# mcat-4cu-b-v2e.net
KiCad netlist of a schematic drawn in EAGLE
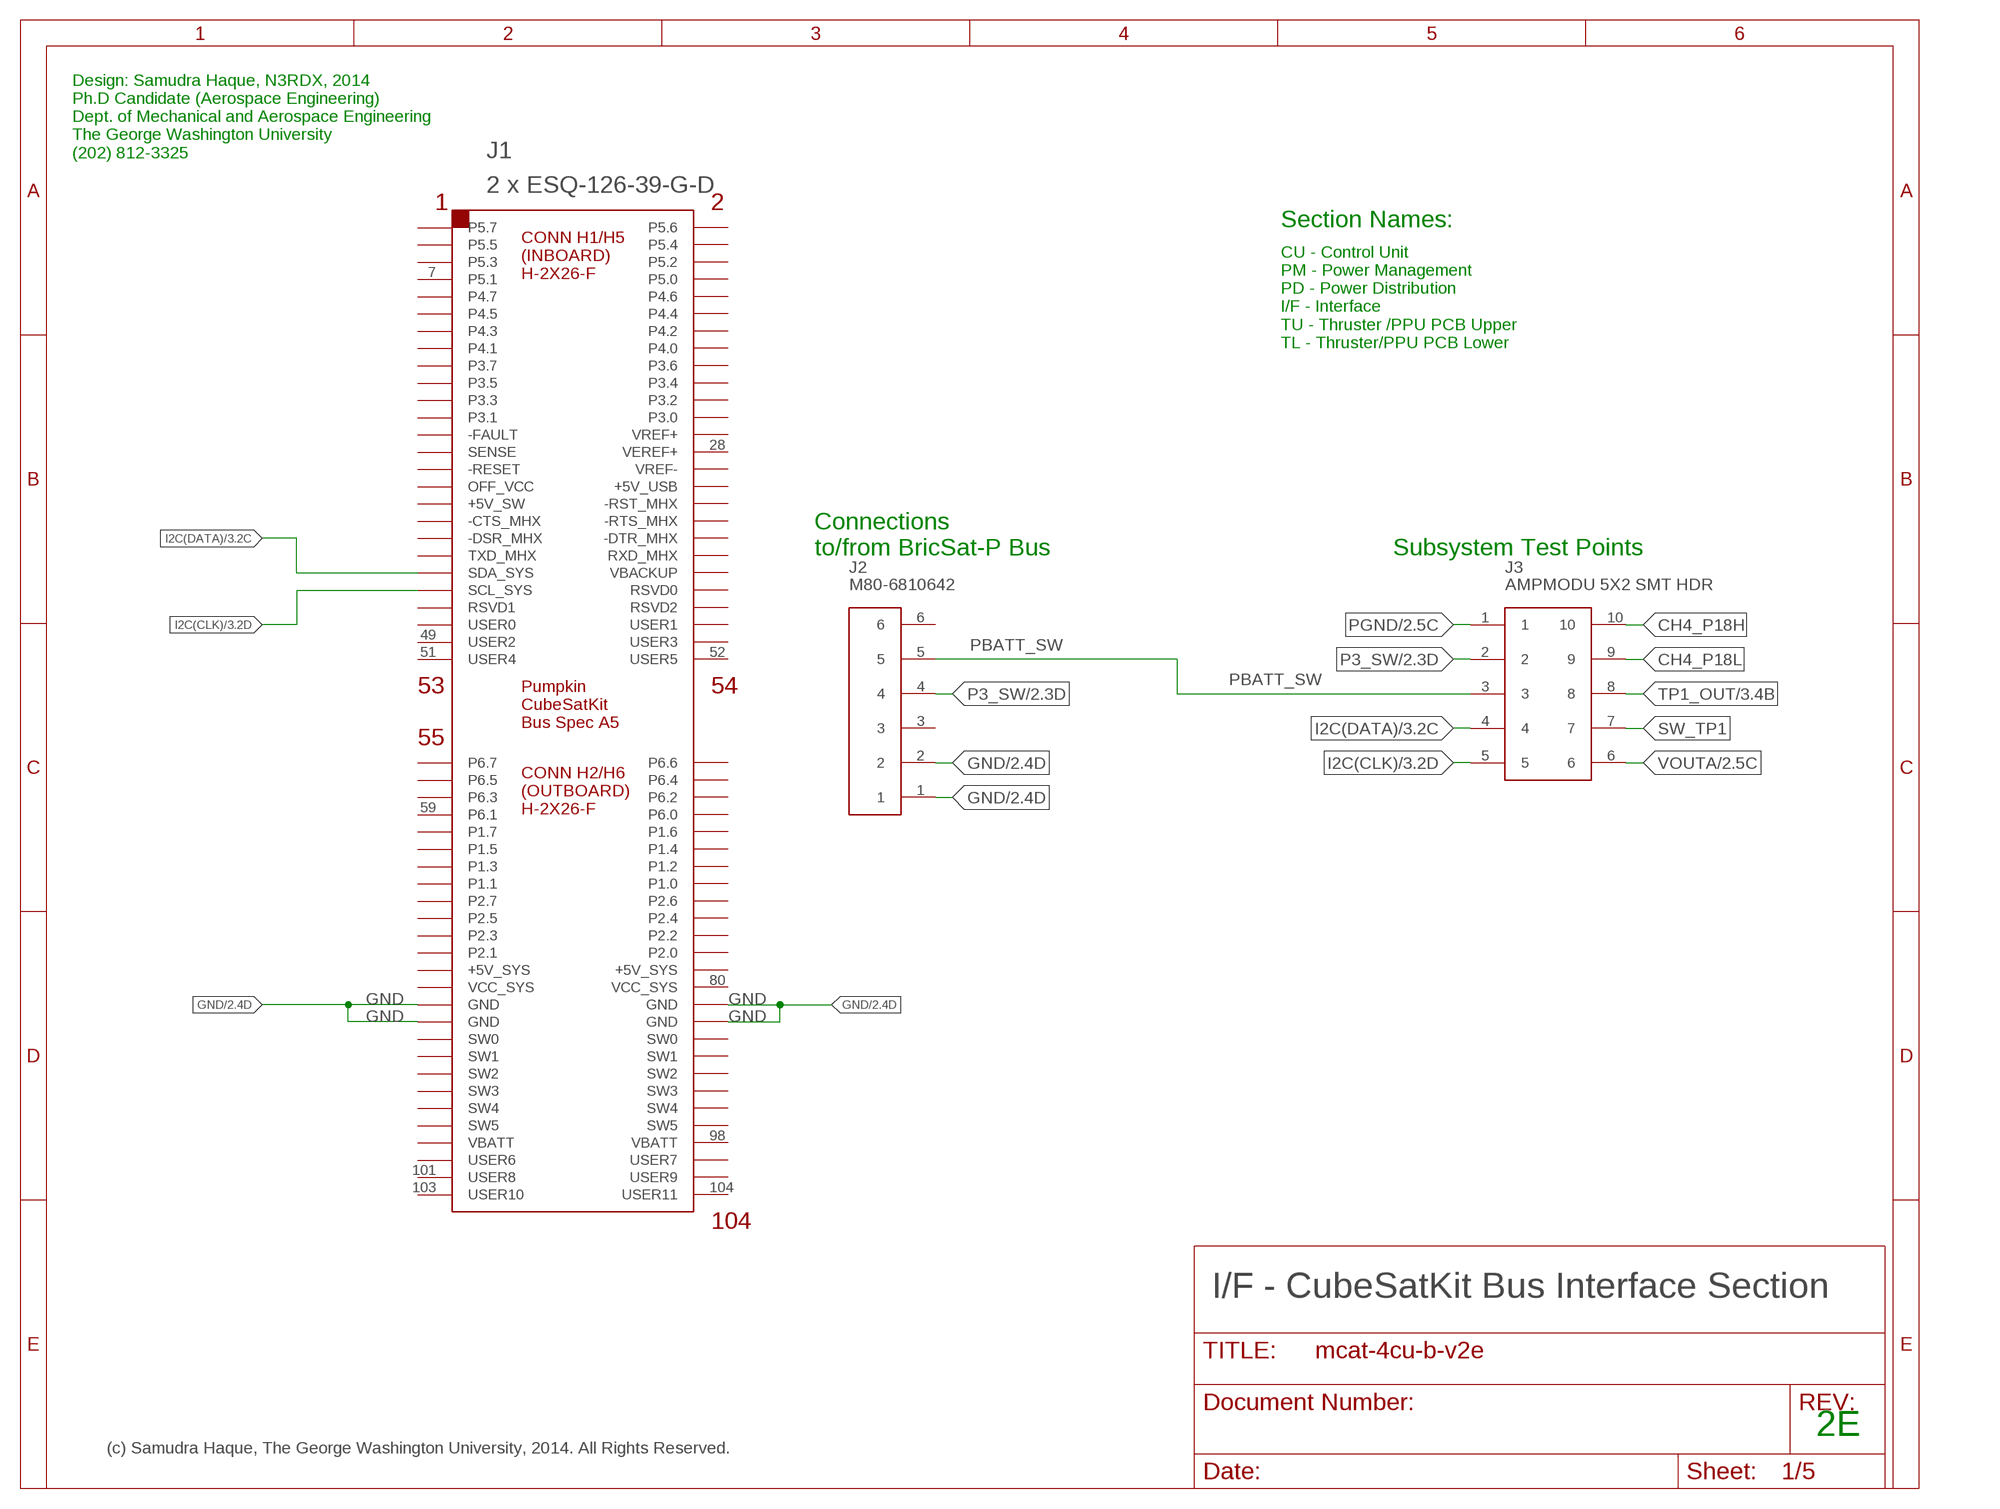
[diagram p0: schematic, sheet 1]
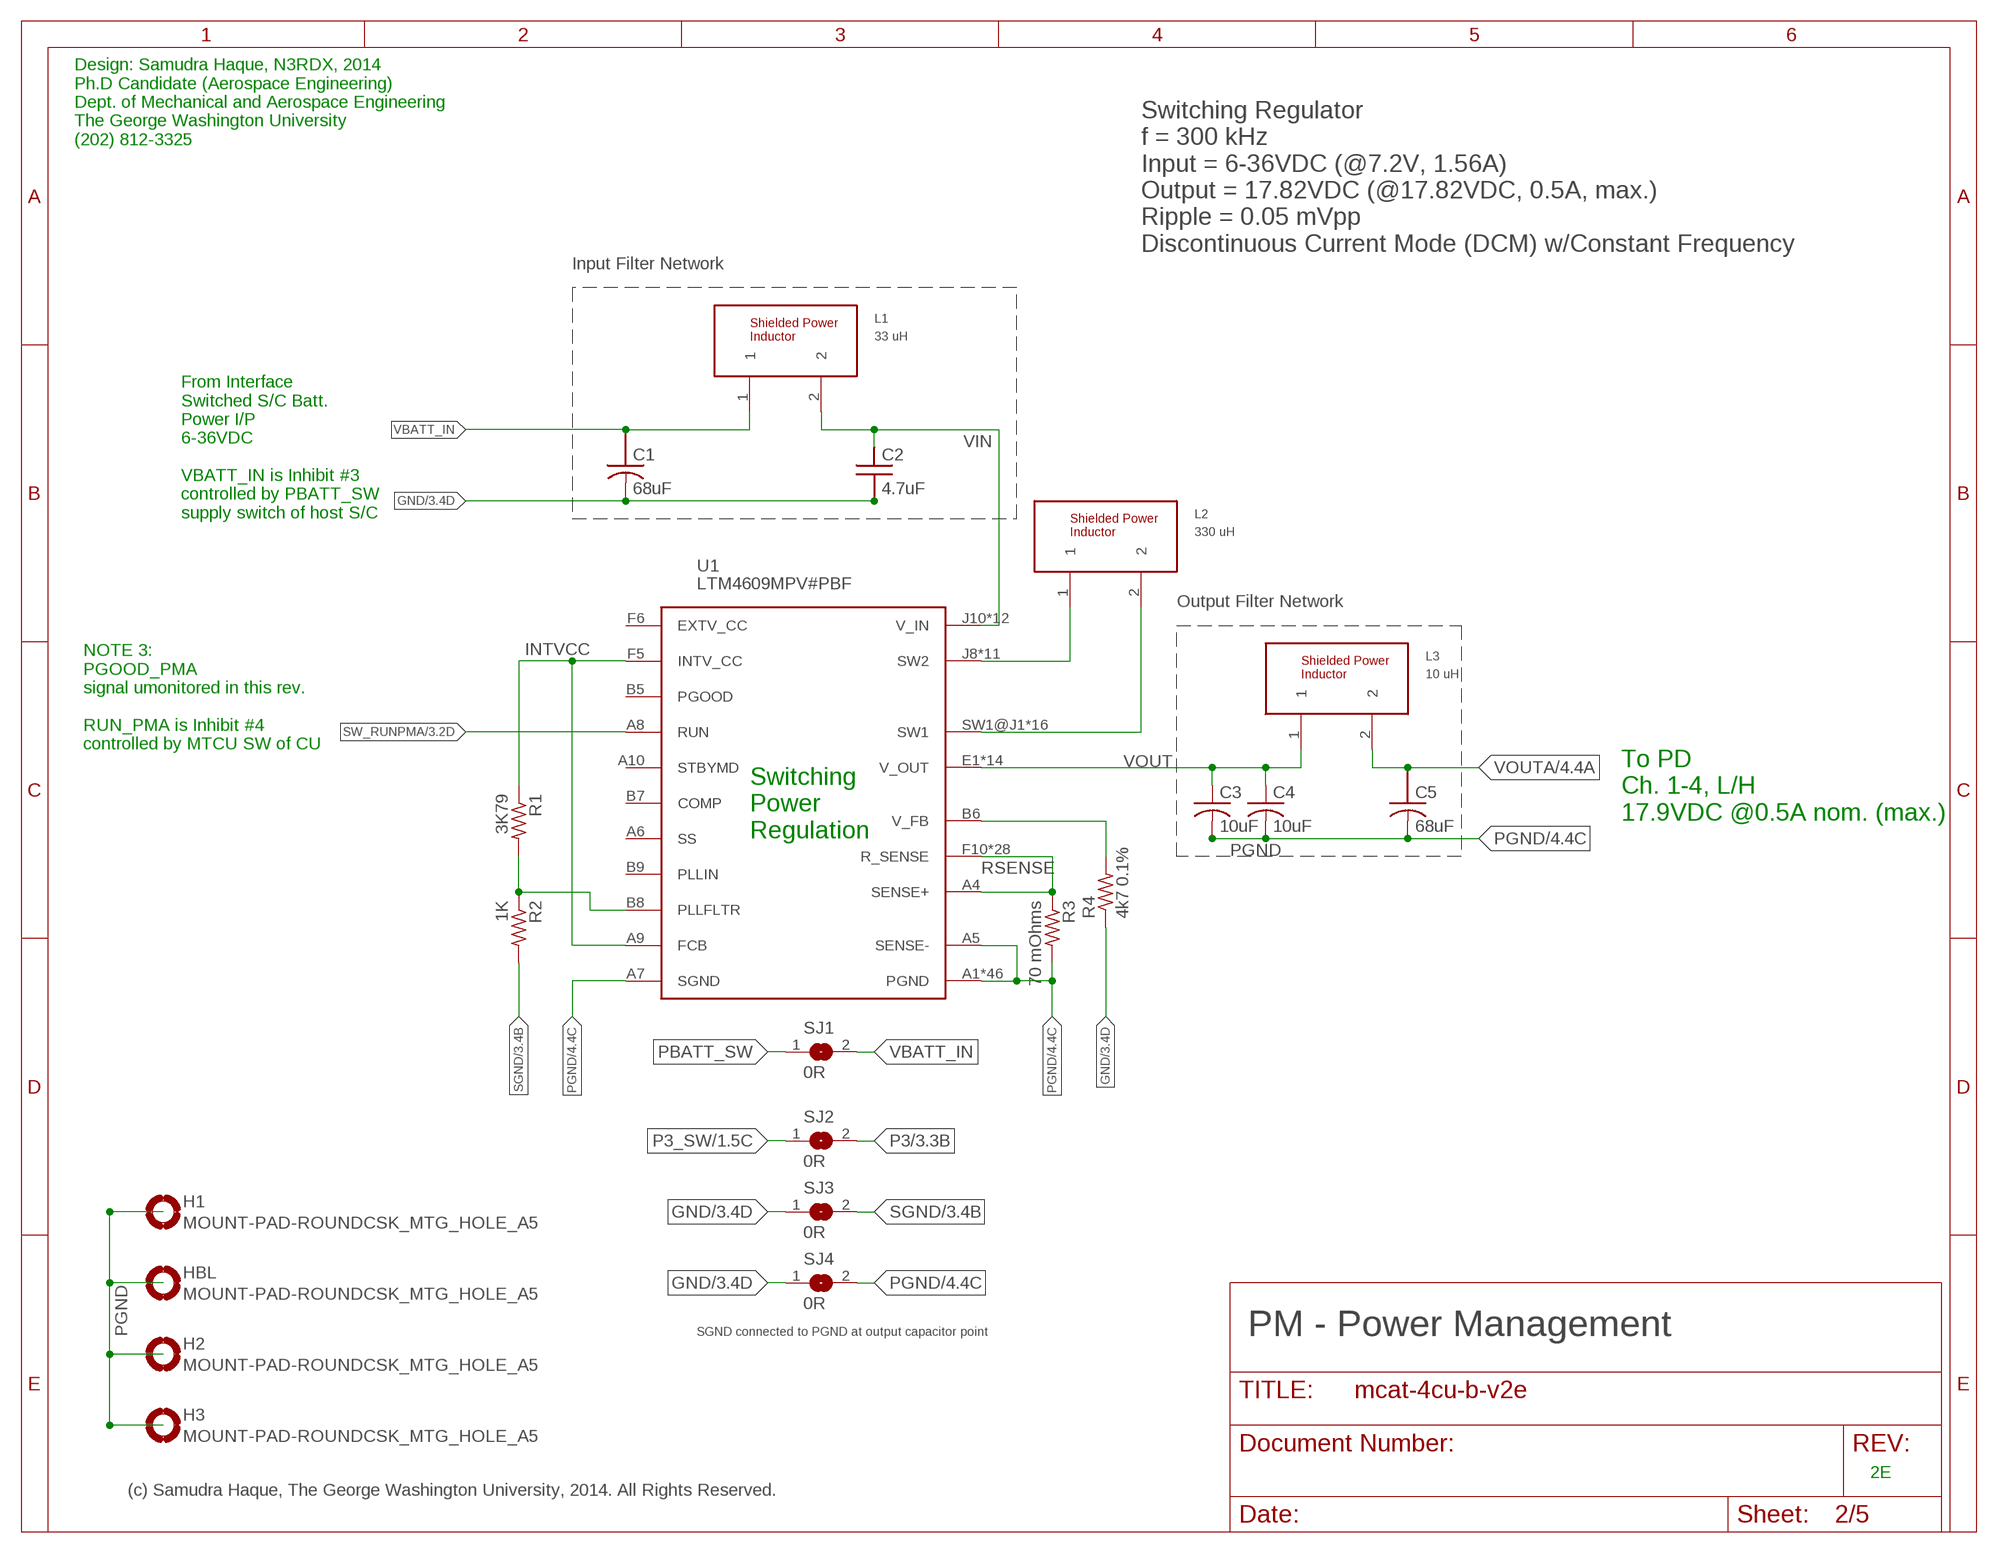
[diagram p1: schematic, sheet 2]
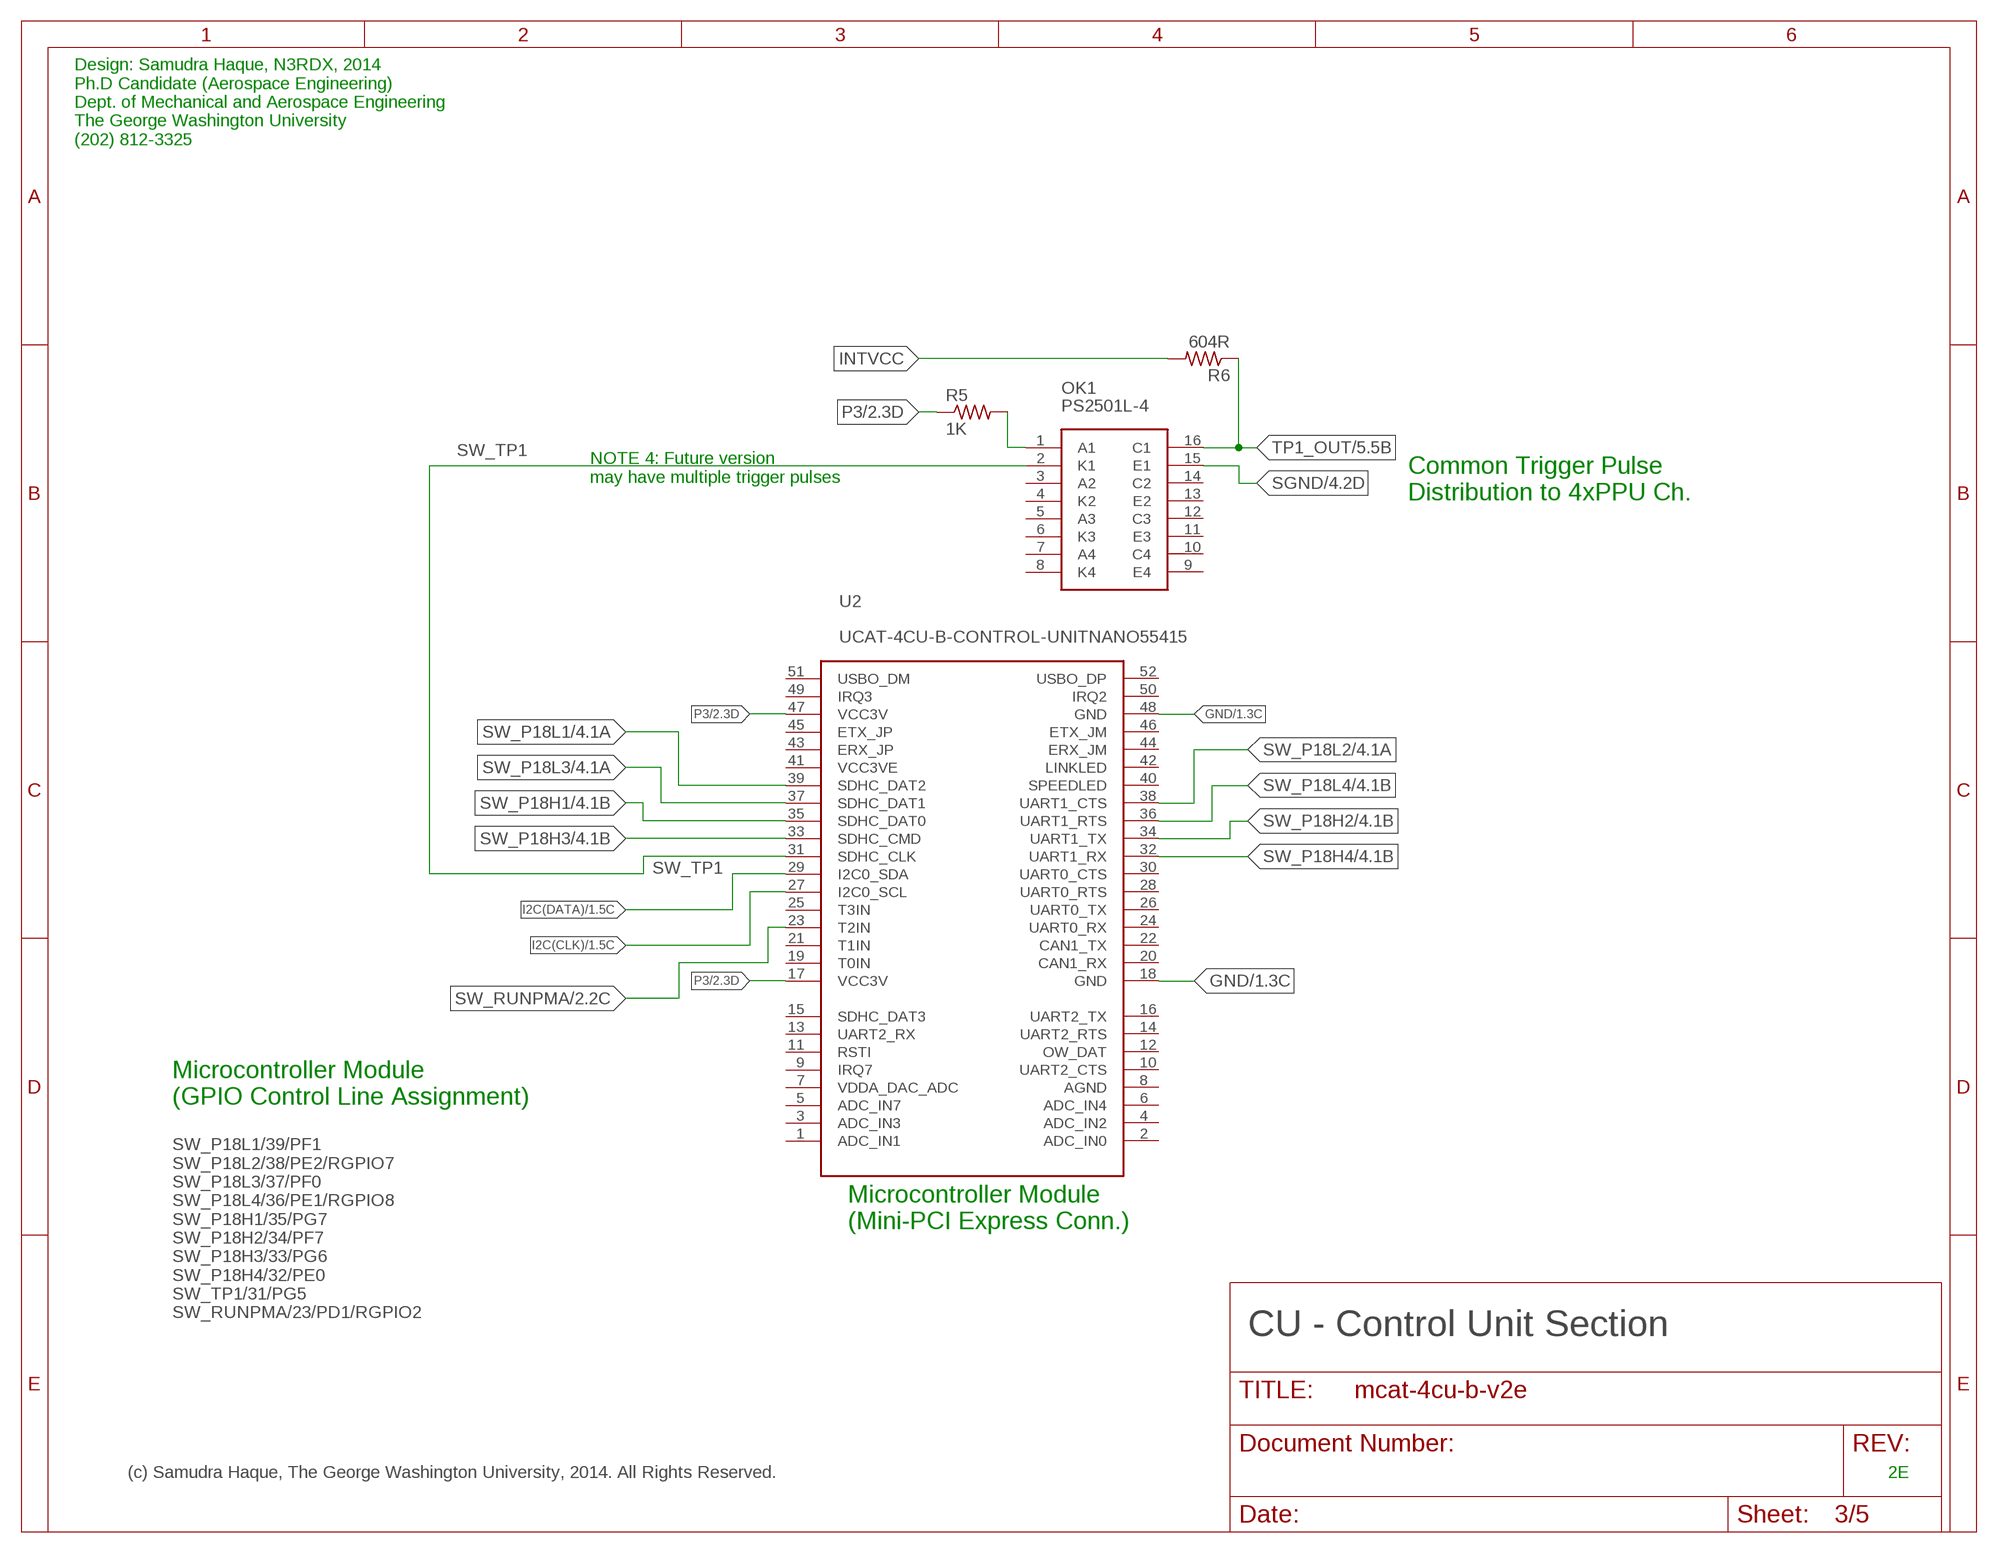
[diagram p2: schematic, sheet 3]
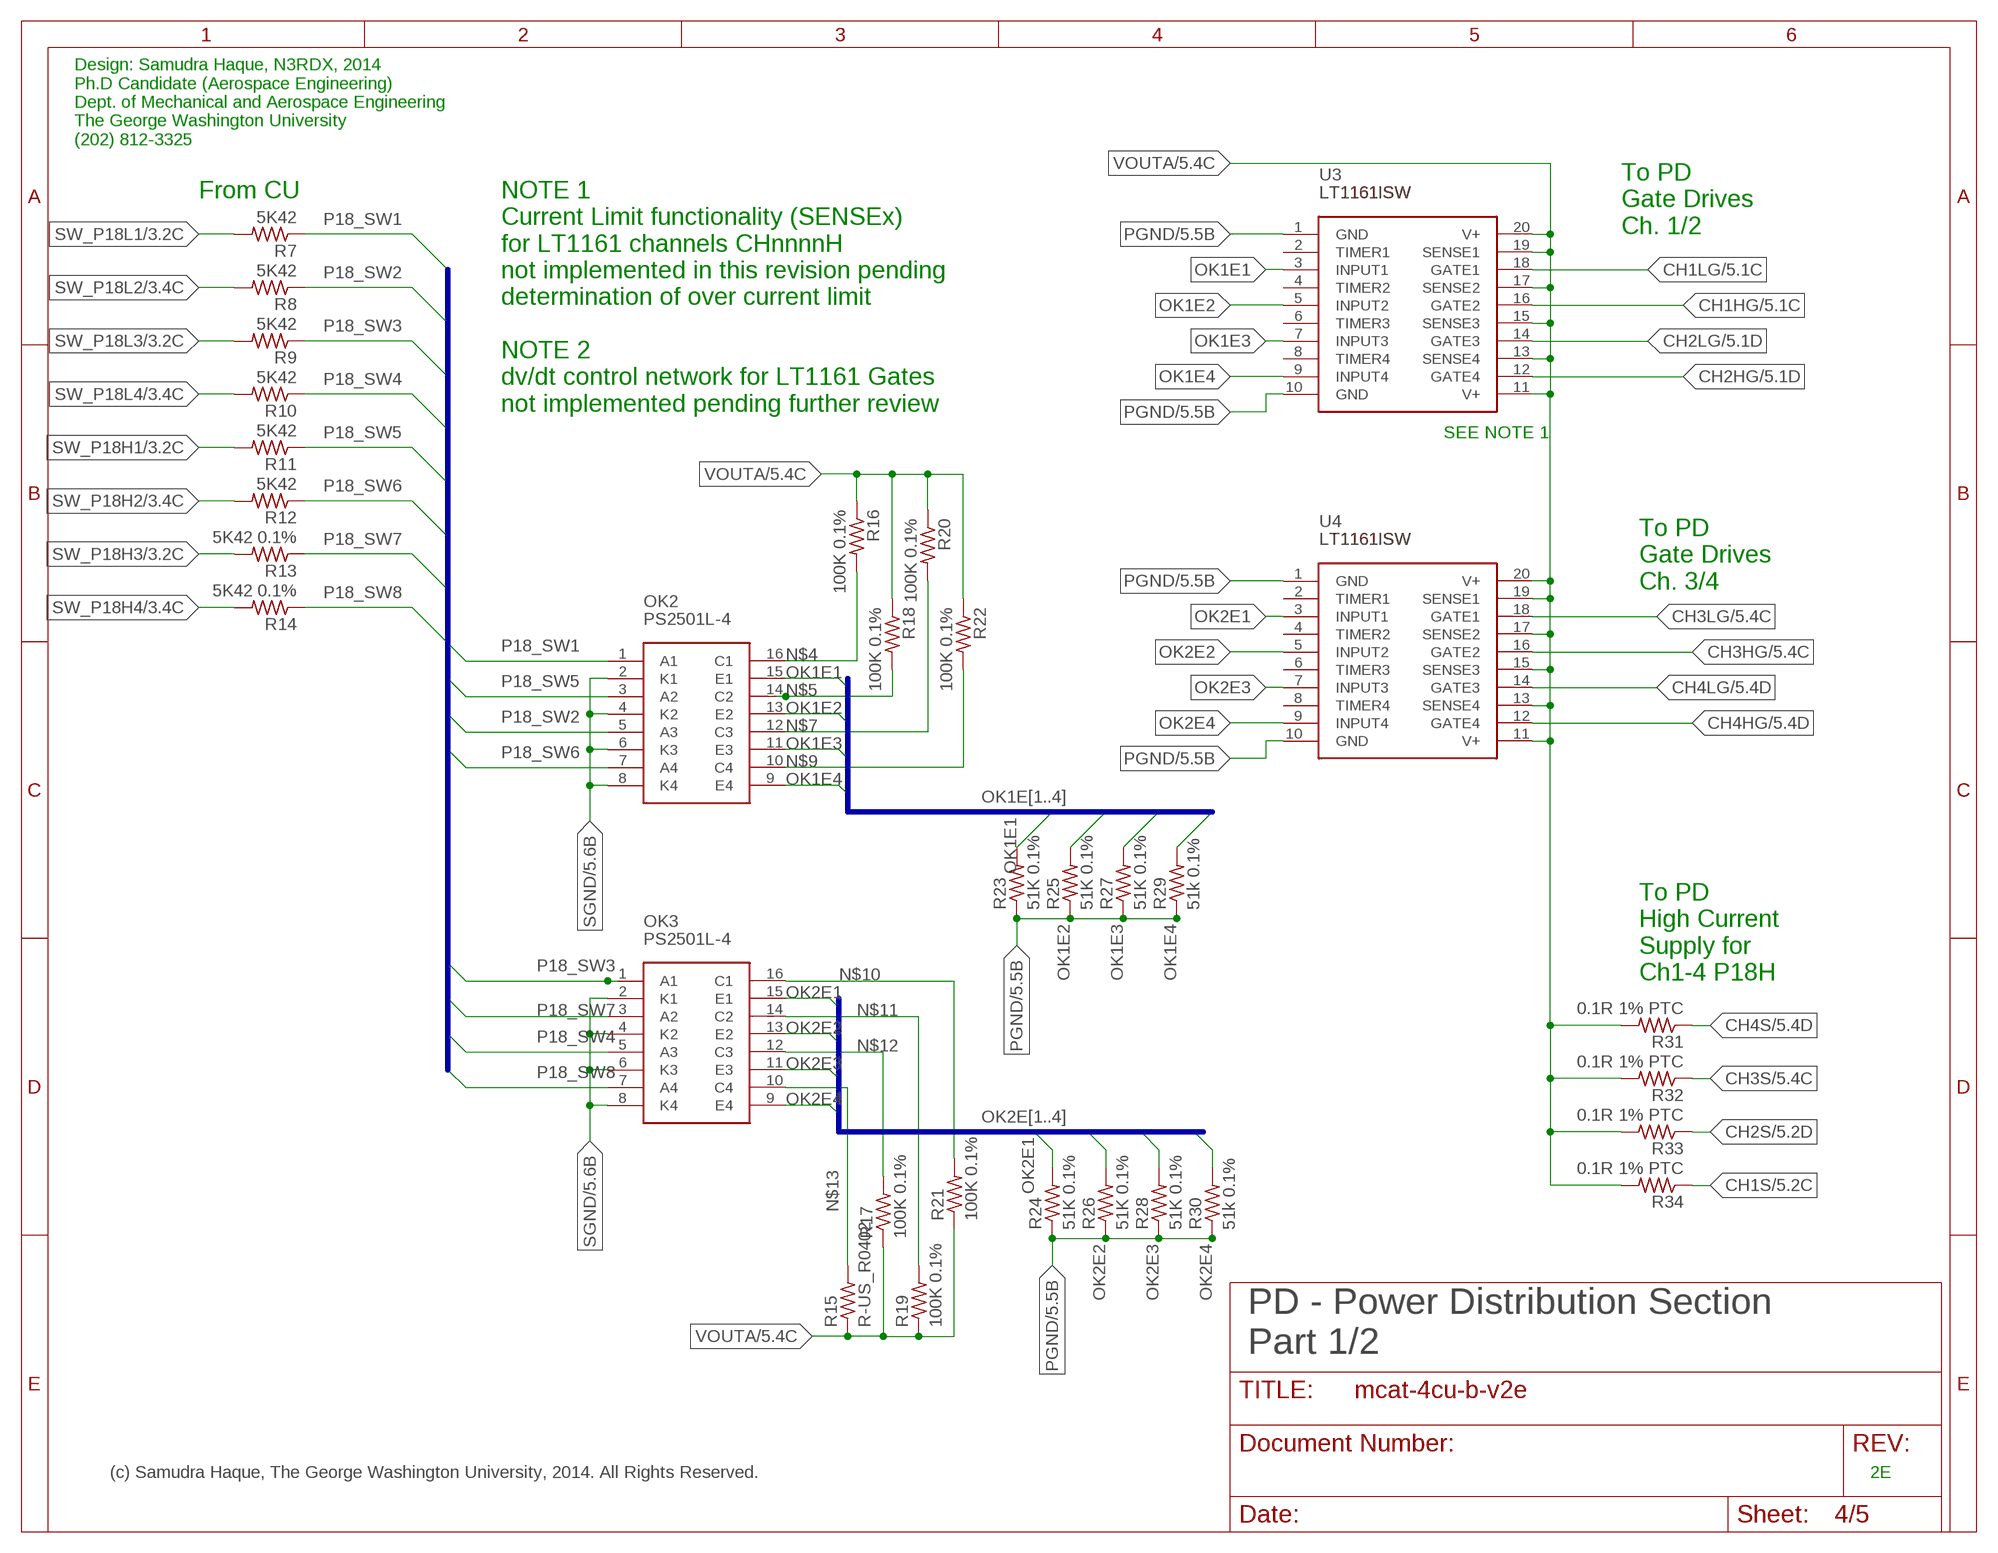
[diagram p3: schematic, sheet 4]
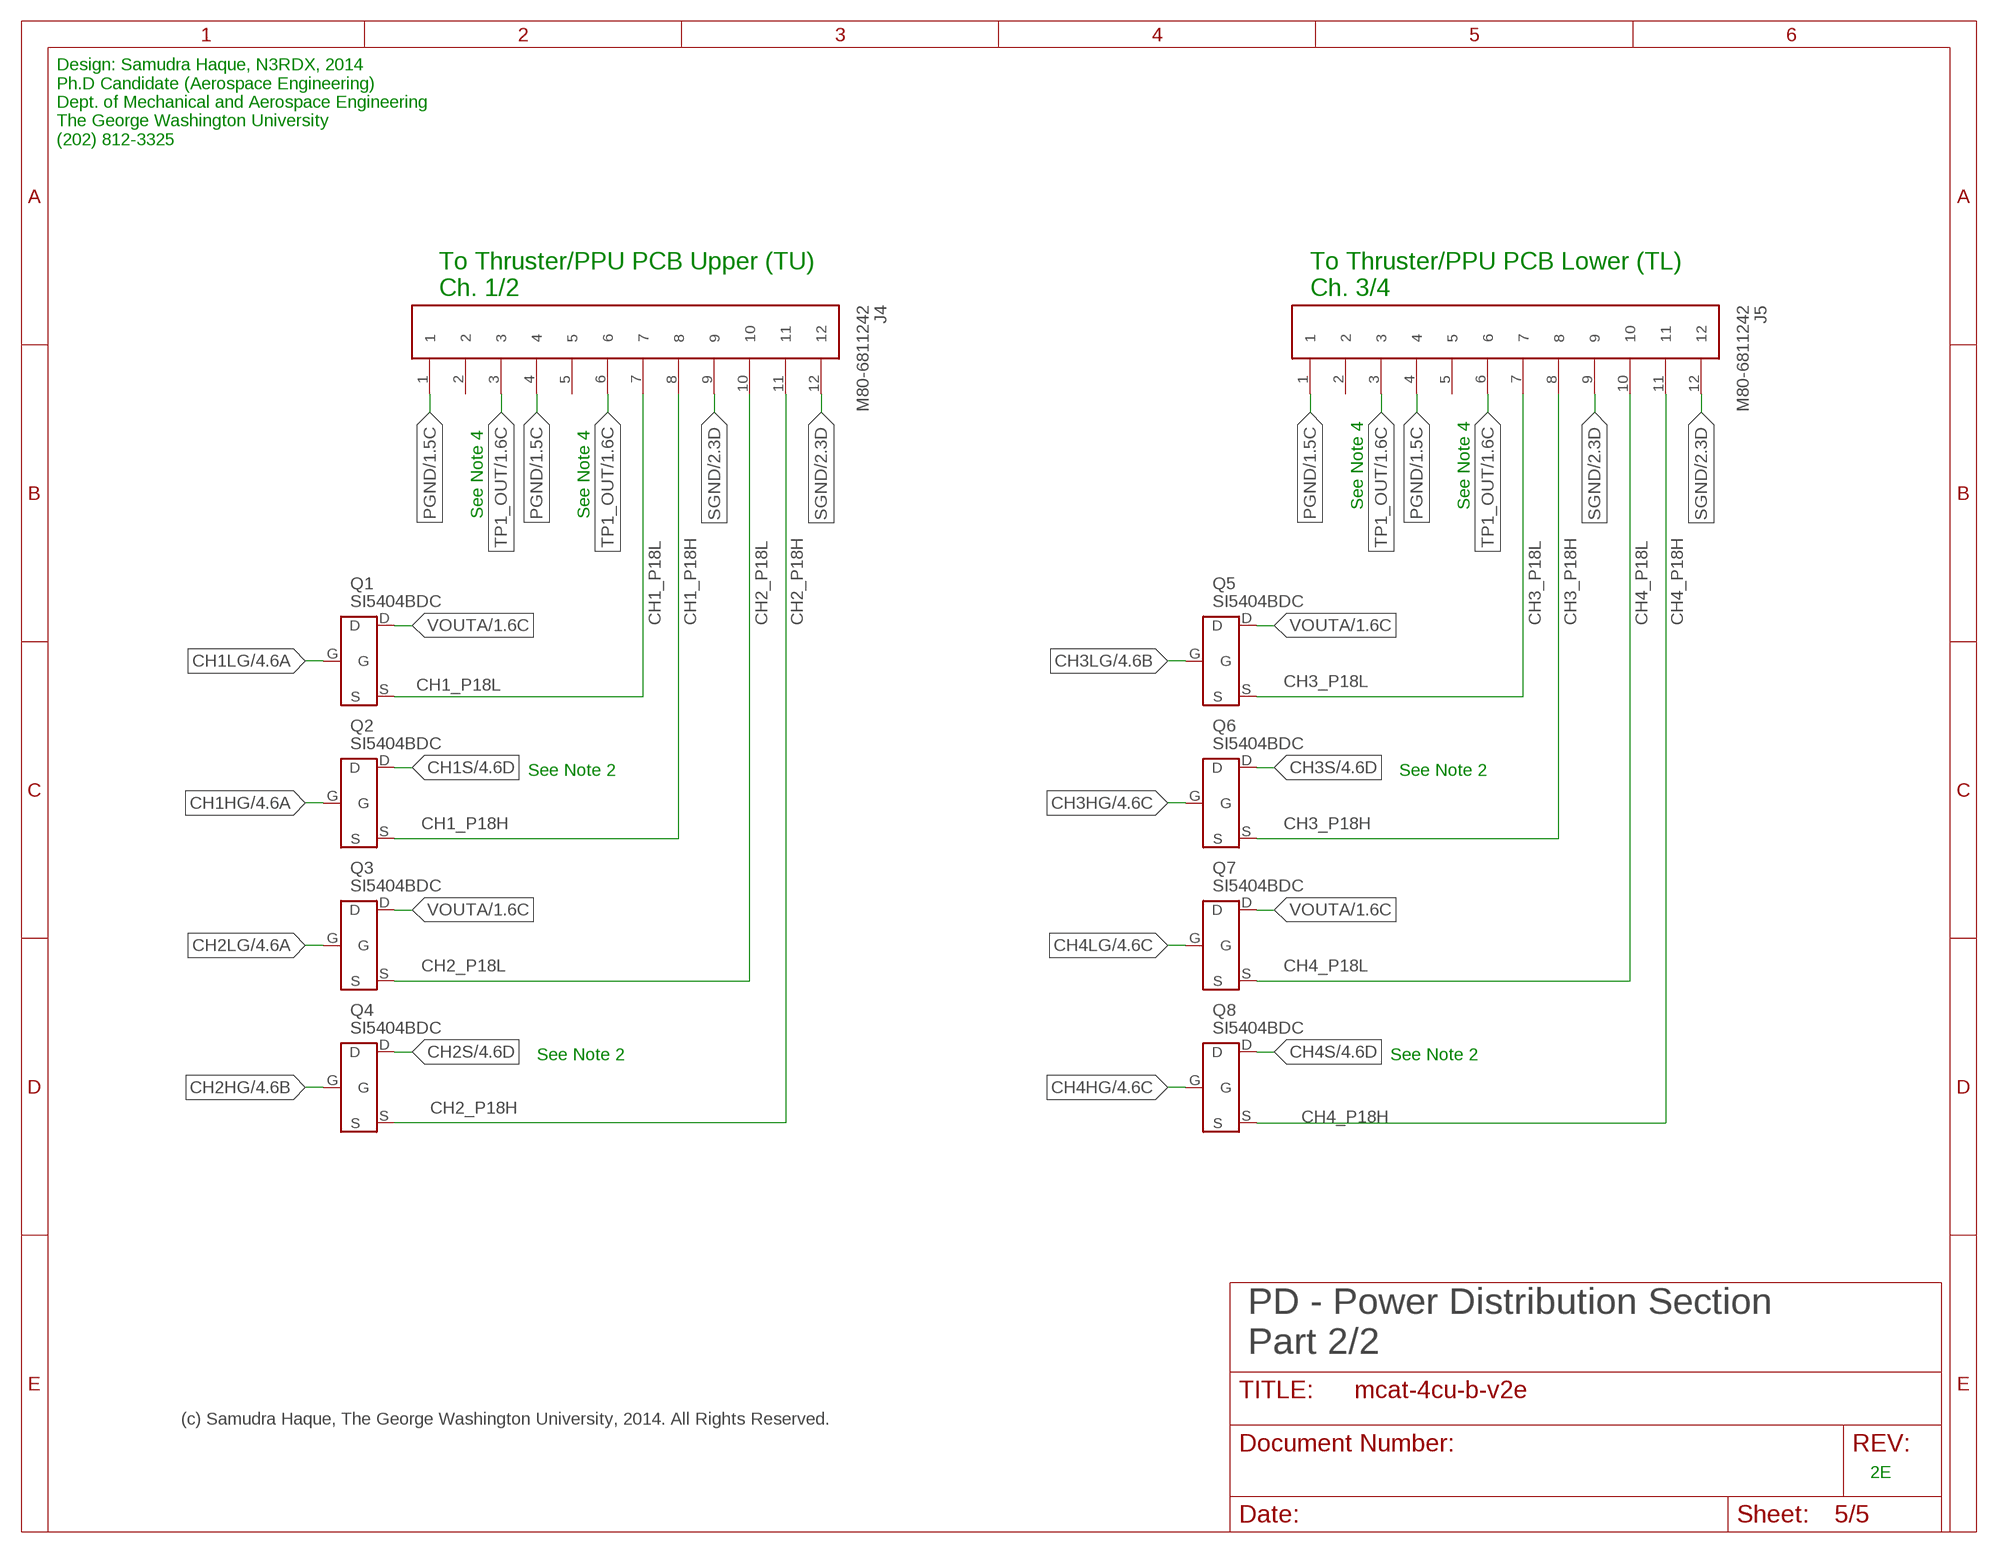
[diagram p4: schematic, sheet 5]

(export (version "E")
  (design (tool "Eeschema 10.0.6"))
  (components
    (comp (ref "J4")
      (value "M80-6811242")
      (footprint "eagle-import:M80-68112")
      (libsource (lib "eagle-import") (part "M80-6811242"))
    )
    (comp (ref "J5")
      (value "M80-6811242")
      (footprint "eagle-import:M80-68112")
      (libsource (lib "eagle-import") (part "M80-6811242"))
    )
    (comp (ref "Q1")
      (value "SI5404BDC")
      (footprint "eagle-import:1206-8-CHIPFET")
      (libsource (lib "eagle-import") (part "SI5404BDC"))
    )
    (comp (ref "Q2")
      (value "SI5404BDC")
      (footprint "eagle-import:1206-8-CHIPFET")
      (libsource (lib "eagle-import") (part "SI5404BDC"))
    )
    (comp (ref "Q3")
      (value "SI5404BDC")
      (footprint "eagle-import:1206-8-CHIPFET")
      (libsource (lib "eagle-import") (part "SI5404BDC"))
    )
    (comp (ref "Q4")
      (value "SI5404BDC")
      (footprint "eagle-import:1206-8-CHIPFET")
      (libsource (lib "eagle-import") (part "SI5404BDC"))
    )
    (comp (ref "Q5")
      (value "SI5404BDC")
      (footprint "eagle-import:1206-8-CHIPFET")
      (libsource (lib "eagle-import") (part "SI5404BDC"))
    )
    (comp (ref "Q6")
      (value "SI5404BDC")
      (footprint "eagle-import:1206-8-CHIPFET")
      (libsource (lib "eagle-import") (part "SI5404BDC"))
    )
    (comp (ref "Q7")
      (value "SI5404BDC")
      (footprint "eagle-import:1206-8-CHIPFET")
      (libsource (lib "eagle-import") (part "SI5404BDC"))
    )
    (comp (ref "Q8")
      (value "SI5404BDC")
      (footprint "eagle-import:1206-8-CHIPFET")
      (libsource (lib "eagle-import") (part "SI5404BDC"))
    )
    (comp (ref "C1")
      (value "68uF")
      (footprint "eagle-import:OS-CON-SVPF-F12")
      (libsource (lib "eagle-import") (part "OSCON-50SVPF68M"))
    )
    (comp (ref "C2")
      (value "4.7uF")
      (footprint "eagle-import:MLCC-X7R-1210")
      (libsource (lib "eagle-import") (part "AVX-LD105C475KAB2A"))
    )
    (comp (ref "C3")
      (value "10uF")
      (footprint "eagle-import:C1210K")
      (libsource (lib "eagle-import") (part "C-USC1210K"))
    )
    (comp (ref "C4")
      (value "10uF")
      (footprint "eagle-import:C1210K")
      (libsource (lib "eagle-import") (part "C-USC1210K"))
    )
    (comp (ref "C5")
      (value "68uF")
      (footprint "eagle-import:OS-CON-SVPF-F12")
      (libsource (lib "eagle-import") (part "OSCON-50SVPF68M"))
    )
    (comp (ref "H1")
      (value "MOUNT-PAD-ROUNDCSK_MTG_HOLE_A5")
      (footprint "eagle-import:CSK_MOUNTING_HOLE")
      (libsource (lib "eagle-import") (part "MOUNT-PAD-ROUNDCSK_MTG_HOLE_A5"))
    )
    (comp (ref "H2")
      (value "MOUNT-PAD-ROUNDCSK_MTG_HOLE_A5")
      (footprint "eagle-import:CSK_MOUNTING_HOLE")
      (libsource (lib "eagle-import") (part "MOUNT-PAD-ROUNDCSK_MTG_HOLE_A5"))
    )
    (comp (ref "H3")
      (value "MOUNT-PAD-ROUNDCSK_MTG_HOLE_A5")
      (footprint "eagle-import:CSK_MOUNTING_HOLE")
      (libsource (lib "eagle-import") (part "MOUNT-PAD-ROUNDCSK_MTG_HOLE_A5"))
    )
    (comp (ref "HBL")
      (value "MOUNT-PAD-ROUNDCSK_MTG_HOLE_A5")
      (footprint "eagle-import:CSK_MOUNTING_HOLE")
      (libsource (lib "eagle-import") (part "MOUNT-PAD-ROUNDCSK_MTG_HOLE_A5"))
    )
    (comp (ref "L1")
      (value "33 uH")
      (footprint "eagle-import:MSS1048")
      (libsource (lib "eagle-import") (part "MSS1038-333ML_"))
    )
    (comp (ref "L2")
      (value "330 uH")
      (footprint "eagle-import:MSS1048")
      (libsource (lib "eagle-import") (part "MSS1048-334KL_"))
    )
    (comp (ref "L3")
      (value "10 uH")
      (footprint "eagle-import:SERIES-POWER-INDUCTORS")
      (fields (field (name "MF") "PANASONIC") (field (name "MPN") "ELL5PS100M"))
      (libsource (lib "eagle-import") (part "ELL-5PS100M"))
    )
    (comp (ref "R1")
      (value "3K79")
      (footprint "eagle-import:R0805")
      (libsource (lib "eagle-import") (part "R-US_R0805"))
    )
    (comp (ref "R2")
      (value "1K")
      (footprint "eagle-import:R0805")
      (libsource (lib "eagle-import") (part "R-US_R0805"))
    )
    (comp (ref "R3")
      (value "70 mOhms")
      (footprint "eagle-import:R1206")
      (libsource (lib "eagle-import") (part "resistor_R-US_R1206"))
    )
    (comp (ref "R4")
      (value "4k7 0.1%")
      (footprint "eagle-import:R0603")
      (libsource (lib "eagle-import") (part "resistor_R-US_R0603"))
    )
    (comp (ref "SJ1") (value "0R") (footprint "eagle-import:SJ") (libsource (lib "eagle-import") (part "SJ")))
    (comp (ref "SJ2") (value "0R") (footprint "eagle-import:SJ") (libsource (lib "eagle-import") (part "SJ")))
    (comp (ref "SJ3") (value "0R") (footprint "eagle-import:SJ") (libsource (lib "eagle-import") (part "SJ")))
    (comp (ref "SJ4") (value "0R") (footprint "eagle-import:SJ") (libsource (lib "eagle-import") (part "SJ")))
    (comp (ref "U1")
      (value "LTM4609MPV#PBF")
      (footprint "eagle-import:LGA-141-LTC-05-08-1840-B")
      (libsource (lib "eagle-import") (part "LTM4609MPV#PBFROHS/HITEMP"))
    )
    (comp (ref "OK2")
      (value "PS2501L-4")
      (footprint "eagle-import:PS2501L-4")
      (libsource (lib "eagle-import") (part "PS2501L-4"))
    )
    (comp (ref "OK3")
      (value "PS2501L-4")
      (footprint "eagle-import:PS2501L-4")
      (libsource (lib "eagle-import") (part "PS2501L-4"))
    )
    (comp (ref "R7")
      (value "5K42")
      (footprint "eagle-import:R1206")
      (libsource (lib "eagle-import") (part "resistor_R-US_R1206"))
    )
    (comp (ref "R8")
      (value "5K42")
      (footprint "eagle-import:R1206")
      (libsource (lib "eagle-import") (part "resistor_R-US_R1206"))
    )
    (comp (ref "R9")
      (value "5K42")
      (footprint "eagle-import:R1206")
      (libsource (lib "eagle-import") (part "resistor_R-US_R1206"))
    )
    (comp (ref "R10")
      (value "5K42")
      (footprint "eagle-import:R1206")
      (libsource (lib "eagle-import") (part "resistor_R-US_R1206"))
    )
    (comp (ref "R11")
      (value "5K42")
      (footprint "eagle-import:R1206")
      (libsource (lib "eagle-import") (part "resistor_R-US_R1206"))
    )
    (comp (ref "R12")
      (value "5K42")
      (footprint "eagle-import:R1206")
      (libsource (lib "eagle-import") (part "resistor_R-US_R1206"))
    )
    (comp (ref "R13")
      (value "5K42 0.1%")
      (footprint "eagle-import:R1206")
      (libsource (lib "eagle-import") (part "resistor_R-US_R1206"))
    )
    (comp (ref "R14")
      (value "5K42 0.1%")
      (footprint "eagle-import:R1206")
      (libsource (lib "eagle-import") (part "resistor_R-US_R1206"))
    )
    (comp (ref "R15")
      (value "R-US_R0402")
      (footprint "eagle-import:R0402")
      (libsource (lib "eagle-import") (part "resistor_R-US_R0402"))
    )
    (comp (ref "R16")
      (value "100K 0.1%")
      (footprint "eagle-import:R0402")
      (libsource (lib "eagle-import") (part "resistor_R-US_R0402"))
    )
    (comp (ref "R17")
      (value "100K 0.1%")
      (footprint "eagle-import:R0402")
      (libsource (lib "eagle-import") (part "resistor_R-US_R0402"))
    )
    (comp (ref "R18")
      (value "100K 0.1%")
      (footprint "eagle-import:R0402")
      (libsource (lib "eagle-import") (part "resistor_R-US_R0402"))
    )
    (comp (ref "R19")
      (value "100K 0.1%")
      (footprint "eagle-import:R0402")
      (libsource (lib "eagle-import") (part "resistor_R-US_R0402"))
    )
    (comp (ref "R20")
      (value "100K 0.1%")
      (footprint "eagle-import:R0402")
      (libsource (lib "eagle-import") (part "resistor_R-US_R0402"))
    )
    (comp (ref "R21")
      (value "100K 0.1%")
      (footprint "eagle-import:R0402")
      (libsource (lib "eagle-import") (part "resistor_R-US_R0402"))
    )
    (comp (ref "R22")
      (value "100K 0.1%")
      (footprint "eagle-import:R0402")
      (libsource (lib "eagle-import") (part "resistor_R-US_R0402"))
    )
    (comp (ref "R23")
      (value "51K 0.1%")
      (footprint "eagle-import:R0603")
      (libsource (lib "eagle-import") (part "resistor_R-US_R0603"))
    )
    (comp (ref "R24")
      (value "51K 0.1%")
      (footprint "eagle-import:R0603")
      (libsource (lib "eagle-import") (part "resistor_R-US_R0603"))
    )
    (comp (ref "R25")
      (value "51K 0.1%")
      (footprint "eagle-import:R0603")
      (libsource (lib "eagle-import") (part "resistor_R-US_R0603"))
    )
    (comp (ref "R26")
      (value "51K 0.1%")
      (footprint "eagle-import:R0603")
      (libsource (lib "eagle-import") (part "resistor_R-US_R0603"))
    )
    (comp (ref "R27")
      (value "51K 0.1%")
      (footprint "eagle-import:R0603")
      (libsource (lib "eagle-import") (part "resistor_R-US_R0603"))
    )
    (comp (ref "R28")
      (value "51K 0.1%")
      (footprint "eagle-import:R0603")
      (libsource (lib "eagle-import") (part "resistor_R-US_R0603"))
    )
    (comp (ref "R29")
      (value "51k 0.1%")
      (footprint "eagle-import:R0603")
      (libsource (lib "eagle-import") (part "resistor_R-US_R0603"))
    )
    (comp (ref "R30")
      (value "51k 0.1%")
      (footprint "eagle-import:R0603")
      (libsource (lib "eagle-import") (part "resistor_R-US_R0603"))
    )
    (comp (ref "R31")
      (value "0.1R 1% PTC")
      (footprint "eagle-import:R0402")
      (libsource (lib "eagle-import") (part "R-US_R0402"))
    )
    (comp (ref "R32")
      (value "0.1R 1% PTC")
      (footprint "eagle-import:R0402")
      (libsource (lib "eagle-import") (part "R-US_R0402"))
    )
    (comp (ref "R33")
      (value "0.1R 1% PTC")
      (footprint "eagle-import:R0402")
      (libsource (lib "eagle-import") (part "R-US_R0402"))
    )
    (comp (ref "R34")
      (value "0.1R 1% PTC")
      (footprint "eagle-import:R0402")
      (libsource (lib "eagle-import") (part "R-US_R0402"))
    )
    (comp (ref "U3")
      (value "LT1161ISW")
      (footprint "eagle-import:20-LEAD-PLASTIC-SO")
      (libsource (lib "eagle-import") (part "LT1161ISW"))
    )
    (comp (ref "U4")
      (value "LT1161ISW")
      (footprint "eagle-import:20-LEAD-PLASTIC-SO")
      (libsource (lib "eagle-import") (part "LT1161ISW"))
    )
    (comp (ref "OK1")
      (value "PS2501L-4")
      (footprint "eagle-import:PS2501L-4")
      (libsource (lib "eagle-import") (part "PS2501L-4"))
    )
    (comp (ref "R5")
      (value "1K")
      (footprint "eagle-import:R0805")
      (libsource (lib "eagle-import") (part "resistor_R-US_R0805"))
    )
    (comp (ref "R6")
      (value "604R")
      (footprint "eagle-import:R0805")
      (libsource (lib "eagle-import") (part "resistor_R-US_R0805"))
    )
    (comp (ref "U2")
      (value "UCAT-4CU-B-CONTROL-UNITNANO55415")
      (footprint "eagle-import:MOLEX-MINI-PCI-EXPRESS-8MM-52CKT")
      (libsource (lib "eagle-import") (part "UCAT-4CU-B-CONTROL-UNITNANO55415"))
    )
    (comp (ref "J1")
      (value "2 x ESQ-126-39-G-D")
      (footprint "eagle-import:CSK-BUS-PKG")
      (libsource (lib "eagle-import") (part "CSK-BUS-CONN2X2X26"))
    )
    (comp (ref "J2")
      (value "M80-6810642")
      (footprint "eagle-import:M80-68106")
      (libsource (lib "eagle-import") (part "M80-6810642"))
    )
    (comp (ref "J3")
      (value "AMPMODU 5X2 SMT HDR")
      (footprint "eagle-import:AMPMODU-SMT-PIN-HEADER-5X2")
      (libsource (lib "eagle-import") (part "AMPMODU-5-146131-X(5X2)"))
    )
  )
  (nets
    (net (code "3") (name "CH1HG") (class "Default")
      (node (ref "Q2") (pin "G") (pinfunction "G_G") (pintype "bidirectional"))
      (node (ref "U3") (pin "16") (pinfunction "GATE2_16") (pintype "bidirectional"))
    )
    (net (code "4") (name "CH1LG") (class "Default")
      (node (ref "Q1") (pin "G") (pinfunction "G_G") (pintype "bidirectional"))
      (node (ref "U3") (pin "18") (pinfunction "GATE1_18") (pintype "bidirectional"))
    )
    (net (code "5") (name "CH1S") (class "Default")
      (node (ref "Q2") (pin "D") (pinfunction "D_D") (pintype "bidirectional"))
      (node (ref "R34") (pin "1") (pinfunction "1_1") (pintype "passive"))
    )
    (net (code "6") (name "CH1_P18H") (class "Default")
      (node (ref "J4") (pin "8") (pinfunction "8_8") (pintype "bidirectional"))
      (node (ref "Q2") (pin "S") (pinfunction "S_S") (pintype "bidirectional"))
    )
    (net (code "7") (name "CH1_P18L") (class "Default")
      (node (ref "J4") (pin "7") (pinfunction "7_7") (pintype "bidirectional"))
      (node (ref "Q1") (pin "S") (pinfunction "S_S") (pintype "bidirectional"))
    )
    (net (code "8") (name "CH2HG") (class "Default")
      (node (ref "Q4") (pin "G") (pinfunction "G_G") (pintype "bidirectional"))
      (node (ref "U3") (pin "12") (pinfunction "GATE4_12") (pintype "bidirectional"))
    )
    (net (code "9") (name "CH2LG") (class "Default")
      (node (ref "Q3") (pin "G") (pinfunction "G_G") (pintype "bidirectional"))
      (node (ref "U3") (pin "14") (pinfunction "GATE3_14") (pintype "bidirectional"))
    )
    (net (code "10") (name "CH2S") (class "Default")
      (node (ref "Q4") (pin "D") (pinfunction "D_D") (pintype "bidirectional"))
      (node (ref "R33") (pin "1") (pinfunction "1_1") (pintype "passive"))
    )
    (net (code "11") (name "CH2_P18H") (class "Default")
      (node (ref "J4") (pin "11") (pinfunction "11_11") (pintype "bidirectional"))
      (node (ref "Q4") (pin "S") (pinfunction "S_S") (pintype "bidirectional"))
    )
    (net (code "12") (name "CH2_P18L") (class "Default")
      (node (ref "J4") (pin "10") (pinfunction "10_10") (pintype "bidirectional"))
      (node (ref "Q3") (pin "S") (pinfunction "S_S") (pintype "bidirectional"))
    )
    (net (code "13") (name "CH3HG") (class "Default")
      (node (ref "Q6") (pin "G") (pinfunction "G_G") (pintype "bidirectional"))
      (node (ref "U4") (pin "16") (pinfunction "GATE2_16") (pintype "bidirectional"))
    )
    (net (code "14") (name "CH3LG") (class "Default")
      (node (ref "Q5") (pin "G") (pinfunction "G_G") (pintype "bidirectional"))
      (node (ref "U4") (pin "18") (pinfunction "GATE1_18") (pintype "bidirectional"))
    )
    (net (code "15") (name "CH3S") (class "Default")
      (node (ref "Q6") (pin "D") (pinfunction "D_D") (pintype "bidirectional"))
      (node (ref "R32") (pin "1") (pinfunction "1_1") (pintype "passive"))
    )
    (net (code "16") (name "CH3_P18H") (class "Default")
      (node (ref "J5") (pin "8") (pinfunction "8_8") (pintype "bidirectional"))
      (node (ref "Q6") (pin "S") (pinfunction "S_S") (pintype "bidirectional"))
    )
    (net (code "17") (name "CH3_P18L") (class "Default")
      (node (ref "J5") (pin "7") (pinfunction "7_7") (pintype "bidirectional"))
      (node (ref "Q5") (pin "S") (pinfunction "S_S") (pintype "bidirectional"))
    )
    (net (code "18") (name "CH4HG") (class "Default")
      (node (ref "Q8") (pin "G") (pinfunction "G_G") (pintype "bidirectional"))
      (node (ref "U4") (pin "12") (pinfunction "GATE4_12") (pintype "bidirectional"))
    )
    (net (code "19") (name "CH4LG") (class "Default")
      (node (ref "Q7") (pin "G") (pinfunction "G_G") (pintype "bidirectional"))
      (node (ref "U4") (pin "14") (pinfunction "GATE3_14") (pintype "bidirectional"))
    )
    (net (code "20") (name "CH4S") (class "Default")
      (node (ref "Q8") (pin "D") (pinfunction "D_D") (pintype "bidirectional"))
      (node (ref "R31") (pin "1") (pinfunction "1_1") (pintype "passive"))
    )
    (net (code "21") (name "CH4_P18H") (class "Default")
      (node (ref "J3") (pin "10") (pinfunction "10_10") (pintype "bidirectional"))
      (node (ref "J5") (pin "11") (pinfunction "11_11") (pintype "bidirectional"))
      (node (ref "Q8") (pin "S") (pinfunction "S_S") (pintype "bidirectional"))
    )
    (net (code "22") (name "CH4_P18L") (class "Default")
      (node (ref "J3") (pin "9") (pinfunction "9_9") (pintype "bidirectional"))
      (node (ref "J5") (pin "10") (pinfunction "10_10") (pintype "bidirectional"))
      (node (ref "Q7") (pin "S") (pinfunction "S_S") (pintype "bidirectional"))
    )
    (net (code "23") (name "GND") (class "Default")
      (node (ref "C1") (pin "K1") (pinfunction "K_K1") (pintype "passive"))
      (node (ref "C2") (pin "2") (pinfunction "2_2") (pintype "passive"))
      (node (ref "J1") (pin "81") (pinfunction "GND_81") (pintype "bidirectional"))
      (node (ref "J1") (pin "82") (pinfunction "GND_82") (pintype "bidirectional"))
      (node (ref "J1") (pin "83") (pinfunction "GND_83") (pintype "bidirectional"))
      (node (ref "J1") (pin "84") (pinfunction "GND_84") (pintype "bidirectional"))
      (node (ref "J2") (pin "1") (pinfunction "1_1") (pintype "bidirectional"))
      (node (ref "J2") (pin "2") (pinfunction "2_2") (pintype "bidirectional"))
      (node (ref "R4") (pin "1") (pinfunction "1_1") (pintype "passive"))
      (node (ref "SJ3") (pin "1") (pinfunction "1_1") (pintype "passive"))
      (node (ref "SJ4") (pin "1") (pinfunction "1_1") (pintype "passive"))
      (node (ref "U2") (pin "18") (pinfunction "GND_18") (pintype "bidirectional"))
      (node (ref "U2") (pin "48") (pinfunction "GND_48") (pintype "bidirectional"))
    )
    (net (code "24") (name "I2C(CLK)") (class "Default")
      (node (ref "J1") (pin "43") (pinfunction "SCL_SYS_43") (pintype "bidirectional"))
      (node (ref "J3") (pin "5") (pinfunction "5_5") (pintype "bidirectional"))
      (node (ref "U2") (pin "27") (pinfunction "I2C0_SCL_27") (pintype "bidirectional"))
    )
    (net (code "25") (name "I2C(DATA)") (class "Default")
      (node (ref "J1") (pin "41") (pinfunction "SDA_SYS_41") (pintype "bidirectional"))
      (node (ref "J3") (pin "4") (pinfunction "4_4") (pintype "bidirectional"))
      (node (ref "U2") (pin "29") (pinfunction "I2C0_SDA_29") (pintype "bidirectional"))
    )
    (net (code "26") (name "INTVCC") (class "Default")
      (node (ref "R1") (pin "1") (pinfunction "1_1") (pintype "passive"))
      (node (ref "R6") (pin "2") (pinfunction "2_2") (pintype "passive"))
      (node (ref "U1") (pin "A9") (pinfunction "FCB_A9") (pintype "bidirectional"))
      (node (ref "U1") (pin "F5") (pinfunction "INTV_CC_F5") (pintype "bidirectional"))
    )
    (net (code "27") (name "N$4") (class "Default")
      (node (ref "OK2") (pin "16") (pinfunction "C1_16") (pintype "bidirectional"))
      (node (ref "R16") (pin "2") (pinfunction "2_2") (pintype "passive"))
    )
    (net (code "28") (name "N$5") (class "Default")
      (node (ref "OK2") (pin "14") (pinfunction "C2_14") (pintype "bidirectional"))
      (node (ref "R18") (pin "2") (pinfunction "2_2") (pintype "passive"))
    )
    (net (code "29") (name "N$7") (class "Default")
      (node (ref "OK2") (pin "12") (pinfunction "C3_12") (pintype "bidirectional"))
      (node (ref "R20") (pin "2") (pinfunction "2_2") (pintype "passive"))
    )
    (net (code "30") (name "N$9") (class "Default")
      (node (ref "OK2") (pin "10") (pinfunction "C4_10") (pintype "bidirectional"))
      (node (ref "R22") (pin "2") (pinfunction "2_2") (pintype "passive"))
    )
    (net (code "31") (name "N$10") (class "Default")
      (node (ref "OK3") (pin "16") (pinfunction "C1_16") (pintype "bidirectional"))
      (node (ref "R21") (pin "2") (pinfunction "2_2") (pintype "passive"))
    )
    (net (code "32") (name "N$11") (class "Default")
      (node (ref "OK3") (pin "14") (pinfunction "C2_14") (pintype "bidirectional"))
      (node (ref "R19") (pin "2") (pinfunction "2_2") (pintype "passive"))
    )
    (net (code "33") (name "N$12") (class "Default")
      (node (ref "OK3") (pin "12") (pinfunction "C3_12") (pintype "bidirectional"))
      (node (ref "R17") (pin "2") (pinfunction "2_2") (pintype "passive"))
    )
    (net (code "34") (name "N$13") (class "Default")
      (node (ref "OK3") (pin "10") (pinfunction "C4_10") (pintype "bidirectional"))
      (node (ref "R15") (pin "2") (pinfunction "2_2") (pintype "passive"))
    )
    (net (code "35") (name "Net-(L2-Pad1)") (class "Default")
      (node (ref "L2") (pin "1") (pinfunction "1_1") (pintype "bidirectional"))
      (node (ref "U1") (pin "J8") (pinfunction "SW2_J8") (pintype "bidirectional"))
      (node (ref "U1") (pin "J9") (pinfunction "SW2_J9") (pintype "bidirectional"))
      (node (ref "U1") (pin "K7") (pinfunction "SW2_K7") (pintype "bidirectional"))
      (node (ref "U1") (pin "K8") (pinfunction "SW2_K8") (pintype "bidirectional"))
      (node (ref "U1") (pin "K9") (pinfunction "SW2_K9") (pintype "bidirectional"))
      (node (ref "U1") (pin "L7") (pinfunction "SW2_L7") (pintype "bidirectional"))
      (node (ref "U1") (pin "L8") (pinfunction "SW2_L8") (pintype "bidirectional"))
      (node (ref "U1") (pin "L9") (pinfunction "SW2_L9") (pintype "bidirectional"))
      (node (ref "U1") (pin "M7") (pinfunction "SW2_M7") (pintype "bidirectional"))
      (node (ref "U1") (pin "M8") (pinfunction "SW2_M8") (pintype "bidirectional"))
      (node (ref "U1") (pin "M9") (pinfunction "SW2_M9") (pintype "bidirectional"))
    )
    (net (code "36") (name "Net-(L2-Pad2)") (class "Default")
      (node (ref "L2") (pin "2") (pinfunction "2_2") (pintype "bidirectional"))
      (node (ref "U1") (pin "SW1@J1") (pinfunction "SW1_SW1@J1") (pintype "bidirectional"))
      (node (ref "U1") (pin "SW1@J2") (pinfunction "SW1_SW1@J2") (pintype "bidirectional"))
      (node (ref "U1") (pin "SW1@J3") (pinfunction "SW1_SW1@J3") (pintype "bidirectional"))
      (node (ref "U1") (pin "SW1@J4") (pinfunction "SW1_SW1@J4") (pintype "bidirectional"))
      (node (ref "U1") (pin "SW1@K1") (pinfunction "SW1_SW1@K1") (pintype "bidirectional"))
      (node (ref "U1") (pin "SW1@K2") (pinfunction "SW1_SW1@K2") (pintype "bidirectional"))
      (node (ref "U1") (pin "SW1@K3") (pinfunction "SW1_SW1@K3") (pintype "bidirectional"))
      (node (ref "U1") (pin "SW1@K4") (pinfunction "SW1_SW1@K4") (pintype "bidirectional"))
      (node (ref "U1") (pin "SW1@L1") (pinfunction "SW1_SW1@L1") (pintype "bidirectional"))
      (node (ref "U1") (pin "SW1@L2") (pinfunction "SW1_SW1@L2") (pintype "bidirectional"))
      (node (ref "U1") (pin "SW1@L3") (pinfunction "SW1_SW1@L3") (pintype "bidirectional"))
      (node (ref "U1") (pin "SW1@L4") (pinfunction "SW1_SW1@L4") (pintype "bidirectional"))
      (node (ref "U1") (pin "SW1@M1") (pinfunction "SW1_SW1@M1") (pintype "bidirectional"))
      (node (ref "U1") (pin "SW1@M2") (pinfunction "SW1_SW1@M2") (pintype "bidirectional"))
      (node (ref "U1") (pin "SW1@M3") (pinfunction "SW1_SW1@M3") (pintype "bidirectional"))
      (node (ref "U1") (pin "SW1@M4") (pinfunction "SW1_SW1@M4") (pintype "bidirectional"))
    )
    (net (code "37") (name "Net-(OK1-A1)") (class "Default")
      (node (ref "OK1") (pin "1") (pinfunction "A1_1") (pintype "bidirectional"))
      (node (ref "R5") (pin "2") (pinfunction "2_2") (pintype "passive"))
    )
    (net (code "38") (name "Net-(U1-PLLFLTR)") (class "Default")
      (node (ref "R1") (pin "2") (pinfunction "2_2") (pintype "passive"))
      (node (ref "R2") (pin "1") (pinfunction "1_1") (pintype "passive"))
      (node (ref "U1") (pin "B8") (pinfunction "PLLFLTR_B8") (pintype "bidirectional"))
    )
    (net (code "39") (name "Net-(U1-V_FB)") (class "Default")
      (node (ref "R4") (pin "2") (pinfunction "2_2") (pintype "passive"))
      (node (ref "U1") (pin "B6") (pinfunction "V_FB_B6") (pintype "bidirectional"))
    )
    (net (code "40") (name "OK1E1") (class "Default")
      (node (ref "OK2") (pin "15") (pinfunction "E1_15") (pintype "bidirectional"))
      (node (ref "R23") (pin "2") (pinfunction "2_2") (pintype "passive"))
      (node (ref "U3") (pin "3") (pinfunction "INPUT1_3") (pintype "bidirectional"))
    )
    (net (code "41") (name "OK1E2") (class "Default")
      (node (ref "OK2") (pin "13") (pinfunction "E2_13") (pintype "bidirectional"))
      (node (ref "R25") (pin "2") (pinfunction "2_2") (pintype "passive"))
      (node (ref "U3") (pin "5") (pinfunction "INPUT2_5") (pintype "bidirectional"))
    )
    (net (code "42") (name "OK1E3") (class "Default")
      (node (ref "OK2") (pin "11") (pinfunction "E3_11") (pintype "bidirectional"))
      (node (ref "R27") (pin "2") (pinfunction "2_2") (pintype "passive"))
      (node (ref "U3") (pin "7") (pinfunction "INPUT3_7") (pintype "bidirectional"))
    )
    (net (code "43") (name "OK1E4") (class "Default")
      (node (ref "OK2") (pin "9") (pinfunction "E4_9") (pintype "bidirectional"))
      (node (ref "R29") (pin "2") (pinfunction "2_2") (pintype "passive"))
      (node (ref "U3") (pin "9") (pinfunction "INPUT4_9") (pintype "bidirectional"))
    )
    (net (code "44") (name "OK2E1") (class "Default")
      (node (ref "OK3") (pin "15") (pinfunction "E1_15") (pintype "bidirectional"))
      (node (ref "R24") (pin "2") (pinfunction "2_2") (pintype "passive"))
      (node (ref "U4") (pin "3") (pinfunction "INPUT1_3") (pintype "bidirectional"))
    )
    (net (code "45") (name "OK2E2") (class "Default")
      (node (ref "OK3") (pin "13") (pinfunction "E2_13") (pintype "bidirectional"))
      (node (ref "R26") (pin "2") (pinfunction "2_2") (pintype "passive"))
      (node (ref "U4") (pin "5") (pinfunction "INPUT2_5") (pintype "bidirectional"))
    )
    (net (code "46") (name "OK2E3") (class "Default")
      (node (ref "OK3") (pin "11") (pinfunction "E3_11") (pintype "bidirectional"))
      (node (ref "R28") (pin "2") (pinfunction "2_2") (pintype "passive"))
      (node (ref "U4") (pin "7") (pinfunction "INPUT3_7") (pintype "bidirectional"))
    )
    (net (code "47") (name "OK2E4") (class "Default")
      (node (ref "OK3") (pin "9") (pinfunction "E4_9") (pintype "bidirectional"))
      (node (ref "R30") (pin "2") (pinfunction "2_2") (pintype "passive"))
      (node (ref "U4") (pin "9") (pinfunction "INPUT4_9") (pintype "bidirectional"))
    )
    (net (code "48") (name "P3") (class "Default")
      (node (ref "R5") (pin "1") (pinfunction "1_1") (pintype "passive"))
      (node (ref "SJ2") (pin "2") (pinfunction "2_2") (pintype "passive"))
      (node (ref "U2") (pin "17") (pinfunction "VCC3V_17") (pintype "bidirectional"))
      (node (ref "U2") (pin "47") (pinfunction "VCC3V_47") (pintype "bidirectional"))
    )
    (net (code "49") (name "P3_SW") (class "Default")
      (node (ref "J2") (pin "4") (pinfunction "4_4") (pintype "bidirectional"))
      (node (ref "J3") (pin "2") (pinfunction "2_2") (pintype "bidirectional"))
      (node (ref "SJ2") (pin "1") (pinfunction "1_1") (pintype "passive"))
    )
    (net (code "50") (name "P18_SW1") (class "Default")
      (node (ref "OK2") (pin "1") (pinfunction "A1_1") (pintype "bidirectional"))
      (node (ref "R7") (pin "1") (pinfunction "1_1") (pintype "passive"))
    )
    (net (code "51") (name "P18_SW2") (class "Default")
      (node (ref "OK2") (pin "5") (pinfunction "A3_5") (pintype "bidirectional"))
      (node (ref "R8") (pin "1") (pinfunction "1_1") (pintype "passive"))
    )
    (net (code "52") (name "P18_SW3") (class "Default")
      (node (ref "OK3") (pin "1") (pinfunction "A1_1") (pintype "bidirectional"))
      (node (ref "R9") (pin "1") (pinfunction "1_1") (pintype "passive"))
    )
    (net (code "53") (name "P18_SW4") (class "Default")
      (node (ref "OK3") (pin "5") (pinfunction "A3_5") (pintype "bidirectional"))
      (node (ref "R10") (pin "1") (pinfunction "1_1") (pintype "passive"))
    )
    (net (code "54") (name "P18_SW5") (class "Default")
      (node (ref "OK2") (pin "3") (pinfunction "A2_3") (pintype "bidirectional"))
      (node (ref "R11") (pin "1") (pinfunction "1_1") (pintype "passive"))
    )
    (net (code "55") (name "P18_SW6") (class "Default")
      (node (ref "OK2") (pin "7") (pinfunction "A4_7") (pintype "bidirectional"))
      (node (ref "R12") (pin "1") (pinfunction "1_1") (pintype "passive"))
    )
    (net (code "56") (name "P18_SW7") (class "Default")
      (node (ref "OK3") (pin "3") (pinfunction "A2_3") (pintype "bidirectional"))
      (node (ref "R13") (pin "1") (pinfunction "1_1") (pintype "passive"))
    )
    (net (code "57") (name "P18_SW8") (class "Default")
      (node (ref "OK3") (pin "7") (pinfunction "A4_7") (pintype "bidirectional"))
      (node (ref "R14") (pin "1") (pinfunction "1_1") (pintype "passive"))
    )
    (net (code "58") (name "PBATT_SW") (class "Default")
      (node (ref "J2") (pin "5") (pinfunction "5_5") (pintype "bidirectional"))
      (node (ref "J3") (pin "3") (pinfunction "3_3") (pintype "bidirectional"))
      (node (ref "SJ1") (pin "1") (pinfunction "1_1") (pintype "passive"))
    )
    (net (code "59") (name "PGND") (class "Default")
      (node (ref "C3") (pin "2") (pinfunction "2_2") (pintype "passive"))
      (node (ref "C4") (pin "2") (pinfunction "2_2") (pintype "passive"))
      (node (ref "C5") (pin "K1") (pinfunction "K_K1") (pintype "passive"))
      (node (ref "H1") (pin "P$1") (pinfunction "MOUNT_P$1") (pintype "passive"))
      (node (ref "H2") (pin "P$1") (pinfunction "MOUNT_P$1") (pintype "passive"))
      (node (ref "H3") (pin "P$1") (pinfunction "MOUNT_P$1") (pintype "passive"))
      (node (ref "HBL") (pin "P$1") (pinfunction "MOUNT_P$1") (pintype "passive"))
      (node (ref "J3") (pin "1") (pinfunction "1_1") (pintype "bidirectional"))
      (node (ref "J4") (pin "1") (pinfunction "1_1") (pintype "bidirectional"))
      (node (ref "J4") (pin "4") (pinfunction "4_4") (pintype "bidirectional"))
      (node (ref "J5") (pin "1") (pinfunction "1_1") (pintype "bidirectional"))
      (node (ref "J5") (pin "4") (pinfunction "4_4") (pintype "bidirectional"))
      (node (ref "R23") (pin "1") (pinfunction "1_1") (pintype "passive"))
      (node (ref "R24") (pin "1") (pinfunction "1_1") (pintype "passive"))
      (node (ref "R25") (pin "1") (pinfunction "1_1") (pintype "passive"))
      (node (ref "R26") (pin "1") (pinfunction "1_1") (pintype "passive"))
      (node (ref "R27") (pin "1") (pinfunction "1_1") (pintype "passive"))
      (node (ref "R28") (pin "1") (pinfunction "1_1") (pintype "passive"))
      (node (ref "R29") (pin "1") (pinfunction "1_1") (pintype "passive"))
      (node (ref "R3") (pin "2") (pinfunction "2_2") (pintype "passive"))
      (node (ref "R30") (pin "1") (pinfunction "1_1") (pintype "passive"))
      (node (ref "SJ4") (pin "2") (pinfunction "2_2") (pintype "passive"))
      (node (ref "U1") (pin "A1") (pinfunction "PGND_A1") (pintype "bidirectional"))
      (node (ref "U1") (pin "A11") (pinfunction "PGND_A11") (pintype "bidirectional"))
      (node (ref "U1") (pin "A12") (pinfunction "PGND_A12") (pintype "bidirectional"))
      (node (ref "U1") (pin "A2") (pinfunction "PGND_A2") (pintype "bidirectional"))
      (node (ref "U1") (pin "A3") (pinfunction "PGND_A3") (pintype "bidirectional"))
      (node (ref "U1") (pin "A5") (pinfunction "SENSE-_A5") (pintype "bidirectional"))
      (node (ref "U1") (pin "A7") (pinfunction "SGND_A7") (pintype "bidirectional"))
      (node (ref "U1") (pin "B1") (pinfunction "PGND_B1") (pintype "bidirectional"))
      (node (ref "U1") (pin "B10") (pinfunction "PGND_B10") (pintype "bidirectional"))
      (node (ref "U1") (pin "B11") (pinfunction "PGND_B11") (pintype "bidirectional"))
      (node (ref "U1") (pin "B12") (pinfunction "PGND_B12") (pintype "bidirectional"))
      (node (ref "U1") (pin "B2") (pinfunction "PGND_B2") (pintype "bidirectional"))
      (node (ref "U1") (pin "B3") (pinfunction "PGND_B3") (pintype "bidirectional"))
      (node (ref "U1") (pin "B4") (pinfunction "PGND_B4") (pintype "bidirectional"))
      (node (ref "U1") (pin "C1") (pinfunction "PGND_C1") (pintype "bidirectional"))
      (node (ref "U1") (pin "C10") (pinfunction "PGND_C10") (pintype "bidirectional"))
      (node (ref "U1") (pin "C11") (pinfunction "PGND_C11") (pintype "bidirectional"))
      (node (ref "U1") (pin "C12") (pinfunction "PGND_C12") (pintype "bidirectional"))
      (node (ref "U1") (pin "C2") (pinfunction "PGND_C2") (pintype "bidirectional"))
      (node (ref "U1") (pin "C3") (pinfunction "PGND_C3") (pintype "bidirectional"))
      (node (ref "U1") (pin "C4") (pinfunction "PGND_C4") (pintype "bidirectional"))
      (node (ref "U1") (pin "C5") (pinfunction "PGND_C5") (pintype "bidirectional"))
      (node (ref "U1") (pin "C6") (pinfunction "PGND_C6") (pintype "bidirectional"))
      (node (ref "U1") (pin "C7") (pinfunction "PGND_C7") (pintype "bidirectional"))
      (node (ref "U1") (pin "C8") (pinfunction "PGND_C8") (pintype "bidirectional"))
      (node (ref "U1") (pin "C9") (pinfunction "PGND_C9") (pintype "bidirectional"))
      (node (ref "U1") (pin "D1") (pinfunction "PGND_D1") (pintype "bidirectional"))
      (node (ref "U1") (pin "D10") (pinfunction "PGND_D10") (pintype "bidirectional"))
      (node (ref "U1") (pin "D11") (pinfunction "PGND_D11") (pintype "bidirectional"))
      (node (ref "U1") (pin "D12") (pinfunction "PGND_D12") (pintype "bidirectional"))
      (node (ref "U1") (pin "D2") (pinfunction "PGND_D2") (pintype "bidirectional"))
      (node (ref "U1") (pin "D3") (pinfunction "PGND_D3") (pintype "bidirectional"))
      (node (ref "U1") (pin "D4") (pinfunction "PGND_D4") (pintype "bidirectional"))
      (node (ref "U1") (pin "D5") (pinfunction "PGND_D5") (pintype "bidirectional"))
      (node (ref "U1") (pin "D6") (pinfunction "PGND_D6") (pintype "bidirectional"))
      (node (ref "U1") (pin "D7") (pinfunction "PGND_D7") (pintype "bidirectional"))
      (node (ref "U1") (pin "D8") (pinfunction "PGND_D8") (pintype "bidirectional"))
      (node (ref "U1") (pin "D9") (pinfunction "PGND_D9") (pintype "bidirectional"))
      (node (ref "U1") (pin "E10") (pinfunction "PGND_E10") (pintype "bidirectional"))
      (node (ref "U1") (pin "E11") (pinfunction "PGND_E11") (pintype "bidirectional"))
      (node (ref "U1") (pin "E12") (pinfunction "PGND_E12") (pintype "bidirectional"))
      (node (ref "U1") (pin "E3") (pinfunction "PGND_E3") (pintype "bidirectional"))
      (node (ref "U1") (pin "E4") (pinfunction "PGND_E4") (pintype "bidirectional"))
      (node (ref "U1") (pin "E5") (pinfunction "PGND_E5") (pintype "bidirectional"))
      (node (ref "U1") (pin "E6") (pinfunction "PGND_E6") (pintype "bidirectional"))
      (node (ref "U1") (pin "E7") (pinfunction "PGND_E7") (pintype "bidirectional"))
      (node (ref "U1") (pin "E8") (pinfunction "PGND_E8") (pintype "bidirectional"))
      (node (ref "U1") (pin "E9") (pinfunction "PGND_E9") (pintype "bidirectional"))
      (node (ref "U3") (pin "1") (pinfunction "GND_1") (pintype "bidirectional"))
      (node (ref "U3") (pin "10") (pinfunction "GND_10") (pintype "bidirectional"))
      (node (ref "U4") (pin "1") (pinfunction "GND_1") (pintype "bidirectional"))
      (node (ref "U4") (pin "10") (pinfunction "GND_10") (pintype "bidirectional"))
    )
    (net (code "60") (name "RSENSE") (class "Default")
      (node (ref "R3") (pin "1") (pinfunction "1_1") (pintype "passive"))
      (node (ref "U1") (pin "A4") (pinfunction "SENSE+_A4") (pintype "bidirectional"))
      (node (ref "U1") (pin "F10") (pinfunction "R_SENSE_F10") (pintype "bidirectional"))
      (node (ref "U1") (pin "F11") (pinfunction "R_SENSE_F11") (pintype "bidirectional"))
      (node (ref "U1") (pin "F12") (pinfunction "R_SENSE_F12") (pintype "bidirectional"))
      (node (ref "U1") (pin "G10") (pinfunction "R_SENSE_G10") (pintype "bidirectional"))
      (node (ref "U1") (pin "G11") (pinfunction "R_SENSE_G11") (pintype "bidirectional"))
      (node (ref "U1") (pin "G12") (pinfunction "R_SENSE_G12") (pintype "bidirectional"))
      (node (ref "U1") (pin "G5") (pinfunction "R_SENSE_G5") (pintype "bidirectional"))
      (node (ref "U1") (pin "G6") (pinfunction "R_SENSE_G6") (pintype "bidirectional"))
      (node (ref "U1") (pin "G7") (pinfunction "R_SENSE_G7") (pintype "bidirectional"))
      (node (ref "U1") (pin "G8") (pinfunction "R_SENSE_G8") (pintype "bidirectional"))
      (node (ref "U1") (pin "G9") (pinfunction "R_SENSE_G9") (pintype "bidirectional"))
      (node (ref "U1") (pin "H10") (pinfunction "R_SENSE_H10") (pintype "bidirectional"))
      (node (ref "U1") (pin "H11") (pinfunction "R_SENSE_H11") (pintype "bidirectional"))
      (node (ref "U1") (pin "H12") (pinfunction "R_SENSE_H12") (pintype "bidirectional"))
      (node (ref "U1") (pin "H5") (pinfunction "R_SENSE_H5") (pintype "bidirectional"))
      (node (ref "U1") (pin "H6") (pinfunction "R_SENSE_H6") (pintype "bidirectional"))
      (node (ref "U1") (pin "H7") (pinfunction "R_SENSE_H7") (pintype "bidirectional"))
      (node (ref "U1") (pin "H8") (pinfunction "R_SENSE_H8") (pintype "bidirectional"))
      (node (ref "U1") (pin "H9") (pinfunction "R_SENSE_H9") (pintype "bidirectional"))
      (node (ref "U1") (pin "J5") (pinfunction "R_SENSE_J5") (pintype "bidirectional"))
      (node (ref "U1") (pin "J6") (pinfunction "R_SENSE_J6") (pintype "bidirectional"))
      (node (ref "U1") (pin "J7") (pinfunction "R_SENSE_J7") (pintype "bidirectional"))
      (node (ref "U1") (pin "K5") (pinfunction "R_SENSE_K5") (pintype "bidirectional"))
      (node (ref "U1") (pin "K6") (pinfunction "R_SENSE_K6") (pintype "bidirectional"))
      (node (ref "U1") (pin "L5") (pinfunction "R_SENSE_L5") (pintype "bidirectional"))
      (node (ref "U1") (pin "L6") (pinfunction "R_SENSE_L6") (pintype "bidirectional"))
      (node (ref "U1") (pin "M5") (pinfunction "R_SENSE_M5") (pintype "bidirectional"))
      (node (ref "U1") (pin "M6") (pinfunction "R_SENSE_M6") (pintype "bidirectional"))
    )
    (net (code "61") (name "SGND") (class "Default")
      (node (ref "J4") (pin "12") (pinfunction "12_12") (pintype "bidirectional"))
      (node (ref "J4") (pin "9") (pinfunction "9_9") (pintype "bidirectional"))
      (node (ref "J5") (pin "12") (pinfunction "12_12") (pintype "bidirectional"))
      (node (ref "J5") (pin "9") (pinfunction "9_9") (pintype "bidirectional"))
      (node (ref "OK1") (pin "15") (pinfunction "E1_15") (pintype "bidirectional"))
      (node (ref "OK2") (pin "2") (pinfunction "K1_2") (pintype "bidirectional"))
      (node (ref "OK2") (pin "4") (pinfunction "K2_4") (pintype "bidirectional"))
      (node (ref "OK2") (pin "6") (pinfunction "K3_6") (pintype "bidirectional"))
      (node (ref "OK2") (pin "8") (pinfunction "K4_8") (pintype "bidirectional"))
      (node (ref "OK3") (pin "2") (pinfunction "K1_2") (pintype "bidirectional"))
      (node (ref "OK3") (pin "4") (pinfunction "K2_4") (pintype "bidirectional"))
      (node (ref "OK3") (pin "6") (pinfunction "K3_6") (pintype "bidirectional"))
      (node (ref "OK3") (pin "8") (pinfunction "K4_8") (pintype "bidirectional"))
      (node (ref "R2") (pin "2") (pinfunction "2_2") (pintype "passive"))
      (node (ref "SJ3") (pin "2") (pinfunction "2_2") (pintype "passive"))
    )
    (net (code "62") (name "SW_P18H1") (class "Default")
      (node (ref "R11") (pin "2") (pinfunction "2_2") (pintype "passive"))
      (node (ref "U2") (pin "35") (pinfunction "SDHC_DAT0_35") (pintype "bidirectional"))
    )
    (net (code "63") (name "SW_P18H2") (class "Default")
      (node (ref "R12") (pin "2") (pinfunction "2_2") (pintype "passive"))
      (node (ref "U2") (pin "34") (pinfunction "UART1_TX_34") (pintype "bidirectional"))
    )
    (net (code "64") (name "SW_P18H3") (class "Default")
      (node (ref "R13") (pin "2") (pinfunction "2_2") (pintype "passive"))
      (node (ref "U2") (pin "33") (pinfunction "SDHC_CMD_33") (pintype "bidirectional"))
    )
    (net (code "65") (name "SW_P18H4") (class "Default")
      (node (ref "R14") (pin "2") (pinfunction "2_2") (pintype "passive"))
      (node (ref "U2") (pin "32") (pinfunction "UART1_RX_32") (pintype "bidirectional"))
    )
    (net (code "66") (name "SW_P18L1") (class "Default")
      (node (ref "R7") (pin "2") (pinfunction "2_2") (pintype "passive"))
      (node (ref "U2") (pin "39") (pinfunction "SDHC_DAT2_39") (pintype "bidirectional"))
    )
    (net (code "67") (name "SW_P18L2") (class "Default")
      (node (ref "R8") (pin "2") (pinfunction "2_2") (pintype "passive"))
      (node (ref "U2") (pin "38") (pinfunction "UART1_CTS_38") (pintype "bidirectional"))
    )
    (net (code "68") (name "SW_P18L3") (class "Default")
      (node (ref "R9") (pin "2") (pinfunction "2_2") (pintype "passive"))
      (node (ref "U2") (pin "37") (pinfunction "SDHC_DAT1_37") (pintype "bidirectional"))
    )
    (net (code "69") (name "SW_P18L4") (class "Default")
      (node (ref "R10") (pin "2") (pinfunction "2_2") (pintype "passive"))
      (node (ref "U2") (pin "36") (pinfunction "UART1_RTS_36") (pintype "bidirectional"))
    )
    (net (code "70") (name "SW_RUNPMA") (class "Default")
      (node (ref "U1") (pin "A8") (pinfunction "RUN_A8") (pintype "bidirectional"))
      (node (ref "U2") (pin "23") (pinfunction "T2IN_23") (pintype "bidirectional"))
    )
    (net (code "71") (name "SW_TP1") (class "Default")
      (node (ref "J3") (pin "7") (pinfunction "7_7") (pintype "bidirectional"))
      (node (ref "OK1") (pin "2") (pinfunction "K1_2") (pintype "bidirectional"))
      (node (ref "U2") (pin "31") (pinfunction "SDHC_CLK_31") (pintype "bidirectional"))
    )
    (net (code "72") (name "TP1_OUT") (class "Default")
      (node (ref "J3") (pin "8") (pinfunction "8_8") (pintype "bidirectional"))
      (node (ref "J4") (pin "3") (pinfunction "3_3") (pintype "bidirectional"))
      (node (ref "J4") (pin "6") (pinfunction "6_6") (pintype "bidirectional"))
      (node (ref "J5") (pin "3") (pinfunction "3_3") (pintype "bidirectional"))
      (node (ref "J5") (pin "6") (pinfunction "6_6") (pintype "bidirectional"))
      (node (ref "OK1") (pin "16") (pinfunction "C1_16") (pintype "bidirectional"))
      (node (ref "R6") (pin "1") (pinfunction "1_1") (pintype "passive"))
    )
    (net (code "73") (name "VBATT_IN") (class "Default")
      (node (ref "C1") (pin "A1") (pinfunction "A_A1") (pintype "passive"))
      (node (ref "L1") (pin "1") (pinfunction "1_1") (pintype "bidirectional"))
      (node (ref "SJ1") (pin "2") (pinfunction "2_2") (pintype "passive"))
    )
    (net (code "74") (name "VIN") (class "Default")
      (node (ref "C2") (pin "1") (pinfunction "1_1") (pintype "passive"))
      (node (ref "L1") (pin "2") (pinfunction "2_2") (pintype "bidirectional"))
      (node (ref "U1") (pin "J10") (pinfunction "V_IN_J10") (pintype "bidirectional"))
      (node (ref "U1") (pin "J11") (pinfunction "V_IN_J11") (pintype "bidirectional"))
      (node (ref "U1") (pin "J12") (pinfunction "V_IN_J12") (pintype "bidirectional"))
      (node (ref "U1") (pin "K10") (pinfunction "V_IN_K10") (pintype "bidirectional"))
      (node (ref "U1") (pin "K11") (pinfunction "V_IN_K11") (pintype "bidirectional"))
      (node (ref "U1") (pin "K12") (pinfunction "V_IN_K12") (pintype "bidirectional"))
      (node (ref "U1") (pin "L10") (pinfunction "V_IN_L10") (pintype "bidirectional"))
      (node (ref "U1") (pin "L11") (pinfunction "V_IN_L11") (pintype "bidirectional"))
      (node (ref "U1") (pin "L12") (pinfunction "V_IN_L12") (pintype "bidirectional"))
      (node (ref "U1") (pin "M10") (pinfunction "V_IN_M10") (pintype "bidirectional"))
      (node (ref "U1") (pin "M11") (pinfunction "V_IN_M11") (pintype "bidirectional"))
      (node (ref "U1") (pin "M12") (pinfunction "V_IN_M12") (pintype "bidirectional"))
    )
    (net (code "75") (name "VOUT") (class "Default")
      (node (ref "C3") (pin "1") (pinfunction "1_1") (pintype "passive"))
      (node (ref "C4") (pin "1") (pinfunction "1_1") (pintype "passive"))
      (node (ref "L3") (pin "1") (pinfunction "1_1") (pintype "bidirectional"))
      (node (ref "U1") (pin "E1") (pinfunction "V_OUT_E1") (pintype "bidirectional"))
      (node (ref "U1") (pin "E2") (pinfunction "V_OUT_E2") (pintype "bidirectional"))
      (node (ref "U1") (pin "F1") (pinfunction "V_OUT_F1") (pintype "bidirectional"))
      (node (ref "U1") (pin "F2") (pinfunction "V_OUT_F2") (pintype "bidirectional"))
      (node (ref "U1") (pin "F3") (pinfunction "V_OUT_F3") (pintype "bidirectional"))
      (node (ref "U1") (pin "F4") (pinfunction "V_OUT_F4") (pintype "bidirectional"))
      (node (ref "U1") (pin "G1") (pinfunction "V_OUT_G1") (pintype "bidirectional"))
      (node (ref "U1") (pin "G2") (pinfunction "V_OUT_G2") (pintype "bidirectional"))
      (node (ref "U1") (pin "G3") (pinfunction "V_OUT_G3") (pintype "bidirectional"))
      (node (ref "U1") (pin "G4") (pinfunction "V_OUT_G4") (pintype "bidirectional"))
      (node (ref "U1") (pin "H2") (pinfunction "V_OUT_H2") (pintype "bidirectional"))
      (node (ref "U1") (pin "H3") (pinfunction "V_OUT_H3") (pintype "bidirectional"))
      (node (ref "U1") (pin "H4") (pinfunction "V_OUT_H4") (pintype "bidirectional"))
      (node (ref "U1") (pin "VOUT") (pinfunction "V_OUT_VOUT") (pintype "bidirectional"))
    )
    (net (code "76") (name "VOUTA") (class "Default")
      (node (ref "C5") (pin "A1") (pinfunction "A_A1") (pintype "passive"))
      (node (ref "J3") (pin "6") (pinfunction "6_6") (pintype "bidirectional"))
      (node (ref "L3") (pin "2") (pinfunction "2_2") (pintype "bidirectional"))
      (node (ref "Q1") (pin "D") (pinfunction "D_D") (pintype "bidirectional"))
      (node (ref "Q3") (pin "D") (pinfunction "D_D") (pintype "bidirectional"))
      (node (ref "Q5") (pin "D") (pinfunction "D_D") (pintype "bidirectional"))
      (node (ref "Q7") (pin "D") (pinfunction "D_D") (pintype "bidirectional"))
      (node (ref "R15") (pin "1") (pinfunction "1_1") (pintype "passive"))
      (node (ref "R16") (pin "1") (pinfunction "1_1") (pintype "passive"))
      (node (ref "R17") (pin "1") (pinfunction "1_1") (pintype "passive"))
      (node (ref "R18") (pin "1") (pinfunction "1_1") (pintype "passive"))
      (node (ref "R19") (pin "1") (pinfunction "1_1") (pintype "passive"))
      (node (ref "R20") (pin "1") (pinfunction "1_1") (pintype "passive"))
      (node (ref "R21") (pin "1") (pinfunction "1_1") (pintype "passive"))
      (node (ref "R22") (pin "1") (pinfunction "1_1") (pintype "passive"))
      (node (ref "R31") (pin "2") (pinfunction "2_2") (pintype "passive"))
      (node (ref "R32") (pin "2") (pinfunction "2_2") (pintype "passive"))
      (node (ref "R33") (pin "2") (pinfunction "2_2") (pintype "passive"))
      (node (ref "R34") (pin "2") (pinfunction "2_2") (pintype "passive"))
      (node (ref "U3") (pin "11") (pinfunction "V+_11") (pintype "bidirectional"))
      (node (ref "U3") (pin "13") (pinfunction "SENSE4_13") (pintype "bidirectional"))
      (node (ref "U3") (pin "15") (pinfunction "SENSE3_15") (pintype "bidirectional"))
      (node (ref "U3") (pin "17") (pinfunction "SENSE2_17") (pintype "bidirectional"))
      (node (ref "U3") (pin "19") (pinfunction "SENSE1_19") (pintype "bidirectional"))
      (node (ref "U3") (pin "20") (pinfunction "V+_20") (pintype "bidirectional"))
      (node (ref "U4") (pin "11") (pinfunction "V+_11") (pintype "bidirectional"))
      (node (ref "U4") (pin "13") (pinfunction "SENSE4_13") (pintype "bidirectional"))
      (node (ref "U4") (pin "15") (pinfunction "SENSE3_15") (pintype "bidirectional"))
      (node (ref "U4") (pin "17") (pinfunction "SENSE2_17") (pintype "bidirectional"))
      (node (ref "U4") (pin "19") (pinfunction "SENSE1_19") (pintype "bidirectional"))
      (node (ref "U4") (pin "20") (pinfunction "V+_20") (pintype "bidirectional"))
    )
    (net (code "77") (name "unconnected-(J1-+5V_SW-Pad33)") (class "Default")
      (node (ref "J1") (pin "33") (pinfunction "+5V_SW_33") (pintype "bidirectional"))
    )
    (net (code "78") (name "unconnected-(J1-+5V_SYS-Pad77)") (class "Default")
      (node (ref "J1") (pin "77") (pinfunction "+5V_SYS_77") (pintype "bidirectional"))
    )
    (net (code "79") (name "unconnected-(J1-+5V_SYS-Pad78)") (class "Default")
      (node (ref "J1") (pin "78") (pinfunction "+5V_SYS_78") (pintype "bidirectional"))
    )
    (net (code "80") (name "unconnected-(J1-+5V_USB-Pad32)") (class "Default")
      (node (ref "J1") (pin "32") (pinfunction "+5V_USB_32") (pintype "bidirectional"))
    )
    (net (code "81") (name "unconnected-(J1--CTS_MHX-Pad35)") (class "Default")
      (node (ref "J1") (pin "35") (pinfunction "-CTS_MHX_35") (pintype "bidirectional"))
    )
    (net (code "82") (name "unconnected-(J1--DSR_MHX-Pad37)") (class "Default")
      (node (ref "J1") (pin "37") (pinfunction "-DSR_MHX_37") (pintype "bidirectional"))
    )
    (net (code "83") (name "unconnected-(J1--DTR_MHX-Pad38)") (class "Default")
      (node (ref "J1") (pin "38") (pinfunction "-DTR_MHX_38") (pintype "bidirectional"))
    )
    (net (code "84") (name "unconnected-(J1--FAULT-Pad25)") (class "Default")
      (node (ref "J1") (pin "25") (pinfunction "-FAULT_25") (pintype "bidirectional"))
    )
    (net (code "85") (name "unconnected-(J1--RESET-Pad29)") (class "Default")
      (node (ref "J1") (pin "29") (pinfunction "-RESET_29") (pintype "bidirectional"))
    )
    (net (code "86") (name "unconnected-(J1--RST_MHX-Pad34)") (class "Default")
      (node (ref "J1") (pin "34") (pinfunction "-RST_MHX_34") (pintype "bidirectional"))
    )
    (net (code "87") (name "unconnected-(J1--RTS_MHX-Pad36)") (class "Default")
      (node (ref "J1") (pin "36") (pinfunction "-RTS_MHX_36") (pintype "bidirectional"))
    )
    (net (code "88") (name "unconnected-(J1-OFF_VCC-Pad31)") (class "Default")
      (node (ref "J1") (pin "31") (pinfunction "OFF_VCC_31") (pintype "bidirectional"))
    )
    (net (code "89") (name "unconnected-(J1-P1.0-Pad68)") (class "Default")
      (node (ref "J1") (pin "68") (pinfunction "P1.0_68") (pintype "bidirectional"))
    )
    (net (code "90") (name "unconnected-(J1-P1.1-Pad67)") (class "Default")
      (node (ref "J1") (pin "67") (pinfunction "P1.1_67") (pintype "bidirectional"))
    )
    (net (code "91") (name "unconnected-(J1-P1.2-Pad66)") (class "Default")
      (node (ref "J1") (pin "66") (pinfunction "P1.2_66") (pintype "bidirectional"))
    )
    (net (code "92") (name "unconnected-(J1-P1.3-Pad65)") (class "Default")
      (node (ref "J1") (pin "65") (pinfunction "P1.3_65") (pintype "bidirectional"))
    )
    (net (code "93") (name "unconnected-(J1-P1.4-Pad64)") (class "Default")
      (node (ref "J1") (pin "64") (pinfunction "P1.4_64") (pintype "bidirectional"))
    )
    (net (code "94") (name "unconnected-(J1-P1.5-Pad63)") (class "Default")
      (node (ref "J1") (pin "63") (pinfunction "P1.5_63") (pintype "bidirectional"))
    )
    (net (code "95") (name "unconnected-(J1-P1.6-Pad62)") (class "Default")
      (node (ref "J1") (pin "62") (pinfunction "P1.6_62") (pintype "bidirectional"))
    )
    (net (code "96") (name "unconnected-(J1-P1.7-Pad61)") (class "Default")
      (node (ref "J1") (pin "61") (pinfunction "P1.7_61") (pintype "bidirectional"))
    )
    (net (code "97") (name "unconnected-(J1-P2.0-Pad76)") (class "Default")
      (node (ref "J1") (pin "76") (pinfunction "P2.0_76") (pintype "bidirectional"))
    )
    (net (code "98") (name "unconnected-(J1-P2.1-Pad75)") (class "Default")
      (node (ref "J1") (pin "75") (pinfunction "P2.1_75") (pintype "bidirectional"))
    )
    (net (code "99") (name "unconnected-(J1-P2.2-Pad74)") (class "Default")
      (node (ref "J1") (pin "74") (pinfunction "P2.2_74") (pintype "bidirectional"))
    )
    (net (code "100") (name "unconnected-(J1-P2.3-Pad73)") (class "Default")
      (node (ref "J1") (pin "73") (pinfunction "P2.3_73") (pintype "bidirectional"))
    )
    (net (code "101") (name "unconnected-(J1-P2.4-Pad72)") (class "Default")
      (node (ref "J1") (pin "72") (pinfunction "P2.4_72") (pintype "bidirectional"))
    )
    (net (code "102") (name "unconnected-(J1-P2.5-Pad71)") (class "Default")
      (node (ref "J1") (pin "71") (pinfunction "P2.5_71") (pintype "bidirectional"))
    )
    (net (code "103") (name "unconnected-(J1-P2.6-Pad70)") (class "Default")
      (node (ref "J1") (pin "70") (pinfunction "P2.6_70") (pintype "bidirectional"))
    )
    (net (code "104") (name "unconnected-(J1-P2.7-Pad69)") (class "Default")
      (node (ref "J1") (pin "69") (pinfunction "P2.7_69") (pintype "bidirectional"))
    )
    (net (code "105") (name "unconnected-(J1-P3.0-Pad24)") (class "Default")
      (node (ref "J1") (pin "24") (pinfunction "P3.0_24") (pintype "bidirectional"))
    )
    (net (code "106") (name "unconnected-(J1-P3.1-Pad23)") (class "Default")
      (node (ref "J1") (pin "23") (pinfunction "P3.1_23") (pintype "bidirectional"))
    )
    (net (code "107") (name "unconnected-(J1-P3.2-Pad22)") (class "Default")
      (node (ref "J1") (pin "22") (pinfunction "P3.2_22") (pintype "bidirectional"))
    )
    (net (code "108") (name "unconnected-(J1-P3.3-Pad21)") (class "Default")
      (node (ref "J1") (pin "21") (pinfunction "P3.3_21") (pintype "bidirectional"))
    )
    (net (code "109") (name "unconnected-(J1-P3.4-Pad20)") (class "Default")
      (node (ref "J1") (pin "20") (pinfunction "P3.4_20") (pintype "bidirectional"))
    )
    (net (code "110") (name "unconnected-(J1-P3.5-Pad19)") (class "Default")
      (node (ref "J1") (pin "19") (pinfunction "P3.5_19") (pintype "bidirectional"))
    )
    (net (code "111") (name "unconnected-(J1-P3.6-Pad18)") (class "Default")
      (node (ref "J1") (pin "18") (pinfunction "P3.6_18") (pintype "bidirectional"))
    )
    (net (code "112") (name "unconnected-(J1-P3.7-Pad17)") (class "Default")
      (node (ref "J1") (pin "17") (pinfunction "P3.7_17") (pintype "bidirectional"))
    )
    (net (code "113") (name "unconnected-(J1-P4.0-Pad16)") (class "Default")
      (node (ref "J1") (pin "16") (pinfunction "P4.0_16") (pintype "bidirectional"))
    )
    (net (code "114") (name "unconnected-(J1-P4.1-Pad15)") (class "Default")
      (node (ref "J1") (pin "15") (pinfunction "P4.1_15") (pintype "bidirectional"))
    )
    (net (code "115") (name "unconnected-(J1-P4.2-Pad14)") (class "Default")
      (node (ref "J1") (pin "14") (pinfunction "P4.2_14") (pintype "bidirectional"))
    )
    (net (code "116") (name "unconnected-(J1-P4.3-Pad13)") (class "Default")
      (node (ref "J1") (pin "13") (pinfunction "P4.3_13") (pintype "bidirectional"))
    )
    (net (code "117") (name "unconnected-(J1-P4.4-Pad12)") (class "Default")
      (node (ref "J1") (pin "12") (pinfunction "P4.4_12") (pintype "bidirectional"))
    )
    (net (code "118") (name "unconnected-(J1-P4.5-Pad11)") (class "Default")
      (node (ref "J1") (pin "11") (pinfunction "P4.5_11") (pintype "bidirectional"))
    )
    (net (code "119") (name "unconnected-(J1-P4.6-Pad10)") (class "Default")
      (node (ref "J1") (pin "10") (pinfunction "P4.6_10") (pintype "bidirectional"))
    )
    (net (code "120") (name "unconnected-(J1-P4.7-Pad9)") (class "Default")
      (node (ref "J1") (pin "9") (pinfunction "P4.7_9") (pintype "bidirectional"))
    )
    (net (code "121") (name "unconnected-(J1-P5.0-Pad8)") (class "Default")
      (node (ref "J1") (pin "8") (pinfunction "P5.0_8") (pintype "bidirectional"))
    )
    (net (code "122") (name "unconnected-(J1-P5.1-Pad7)") (class "Default")
      (node (ref "J1") (pin "7") (pinfunction "P5.1_7") (pintype "bidirectional"))
    )
    (net (code "123") (name "unconnected-(J1-P5.2-Pad6)") (class "Default")
      (node (ref "J1") (pin "6") (pinfunction "P5.2_6") (pintype "bidirectional"))
    )
    (net (code "124") (name "unconnected-(J1-P5.3-Pad5)") (class "Default")
      (node (ref "J1") (pin "5") (pinfunction "P5.3_5") (pintype "bidirectional"))
    )
    (net (code "125") (name "unconnected-(J1-P5.4-Pad4)") (class "Default")
      (node (ref "J1") (pin "4") (pinfunction "P5.4_4") (pintype "bidirectional"))
    )
    (net (code "126") (name "unconnected-(J1-P5.5-Pad3)") (class "Default")
      (node (ref "J1") (pin "3") (pinfunction "P5.5_3") (pintype "bidirectional"))
    )
    (net (code "127") (name "unconnected-(J1-P5.6-Pad2)") (class "Default")
      (node (ref "J1") (pin "2") (pinfunction "P5.6_2") (pintype "bidirectional"))
    )
    (net (code "128") (name "unconnected-(J1-P5.7-Pad1)") (class "Default")
      (node (ref "J1") (pin "1") (pinfunction "P5.7_1") (pintype "bidirectional"))
    )
    (net (code "129") (name "unconnected-(J1-P6.0-Pad60)") (class "Default")
      (node (ref "J1") (pin "60") (pinfunction "P6.0_60") (pintype "bidirectional"))
    )
    (net (code "130") (name "unconnected-(J1-P6.1-Pad59)") (class "Default")
      (node (ref "J1") (pin "59") (pinfunction "P6.1_59") (pintype "bidirectional"))
    )
    (net (code "131") (name "unconnected-(J1-P6.2-Pad58)") (class "Default")
      (node (ref "J1") (pin "58") (pinfunction "P6.2_58") (pintype "bidirectional"))
    )
    (net (code "132") (name "unconnected-(J1-P6.3-Pad57)") (class "Default")
      (node (ref "J1") (pin "57") (pinfunction "P6.3_57") (pintype "bidirectional"))
    )
    (net (code "133") (name "unconnected-(J1-P6.4-Pad56)") (class "Default")
      (node (ref "J1") (pin "56") (pinfunction "P6.4_56") (pintype "bidirectional"))
    )
    (net (code "134") (name "unconnected-(J1-P6.5-Pad55)") (class "Default")
      (node (ref "J1") (pin "55") (pinfunction "P6.5_55") (pintype "bidirectional"))
    )
    (net (code "135") (name "unconnected-(J1-P6.6-Pad54)") (class "Default")
      (node (ref "J1") (pin "54") (pinfunction "P6.6_54") (pintype "bidirectional"))
    )
    (net (code "136") (name "unconnected-(J1-P6.7-Pad53)") (class "Default")
      (node (ref "J1") (pin "53") (pinfunction "P6.7_53") (pintype "bidirectional"))
    )
    (net (code "137") (name "unconnected-(J1-RSVD0-Pad44)") (class "Default")
      (node (ref "J1") (pin "44") (pinfunction "RSVD0_44") (pintype "bidirectional"))
    )
    (net (code "138") (name "unconnected-(J1-RSVD1-Pad45)") (class "Default")
      (node (ref "J1") (pin "45") (pinfunction "RSVD1_45") (pintype "bidirectional"))
    )
    (net (code "139") (name "unconnected-(J1-RSVD2-Pad46)") (class "Default")
      (node (ref "J1") (pin "46") (pinfunction "RSVD2_46") (pintype "bidirectional"))
    )
    (net (code "140") (name "unconnected-(J1-RXD_MHX-Pad40)") (class "Default")
      (node (ref "J1") (pin "40") (pinfunction "RXD_MHX_40") (pintype "bidirectional"))
    )
    (net (code "141") (name "unconnected-(J1-SENSE-Pad27)") (class "Default")
      (node (ref "J1") (pin "27") (pinfunction "SENSE_27") (pintype "bidirectional"))
    )
    (net (code "142") (name "unconnected-(J1-SW0-Pad85)") (class "Default")
      (node (ref "J1") (pin "85") (pinfunction "SW0_85") (pintype "bidirectional"))
    )
    (net (code "143") (name "unconnected-(J1-SW0-Pad86)") (class "Default")
      (node (ref "J1") (pin "86") (pinfunction "SW0_86") (pintype "bidirectional"))
    )
    (net (code "144") (name "unconnected-(J1-SW1-Pad87)") (class "Default")
      (node (ref "J1") (pin "87") (pinfunction "SW1_87") (pintype "bidirectional"))
    )
    (net (code "145") (name "unconnected-(J1-SW1-Pad88)") (class "Default")
      (node (ref "J1") (pin "88") (pinfunction "SW1_88") (pintype "bidirectional"))
    )
    (net (code "146") (name "unconnected-(J1-SW2-Pad89)") (class "Default")
      (node (ref "J1") (pin "89") (pinfunction "SW2_89") (pintype "bidirectional"))
    )
    (net (code "147") (name "unconnected-(J1-SW2-Pad90)") (class "Default")
      (node (ref "J1") (pin "90") (pinfunction "SW2_90") (pintype "bidirectional"))
    )
    (net (code "148") (name "unconnected-(J1-SW3-Pad91)") (class "Default")
      (node (ref "J1") (pin "91") (pinfunction "SW3_91") (pintype "bidirectional"))
    )
    (net (code "149") (name "unconnected-(J1-SW3-Pad92)") (class "Default")
      (node (ref "J1") (pin "92") (pinfunction "SW3_92") (pintype "bidirectional"))
    )
    (net (code "150") (name "unconnected-(J1-SW4-Pad93)") (class "Default")
      (node (ref "J1") (pin "93") (pinfunction "SW4_93") (pintype "bidirectional"))
    )
    (net (code "151") (name "unconnected-(J1-SW4-Pad94)") (class "Default")
      (node (ref "J1") (pin "94") (pinfunction "SW4_94") (pintype "bidirectional"))
    )
    (net (code "152") (name "unconnected-(J1-SW5-Pad95)") (class "Default")
      (node (ref "J1") (pin "95") (pinfunction "SW5_95") (pintype "bidirectional"))
    )
    (net (code "153") (name "unconnected-(J1-SW5-Pad96)") (class "Default")
      (node (ref "J1") (pin "96") (pinfunction "SW5_96") (pintype "bidirectional"))
    )
    (net (code "154") (name "unconnected-(J1-TXD_MHX-Pad39)") (class "Default")
      (node (ref "J1") (pin "39") (pinfunction "TXD_MHX_39") (pintype "bidirectional"))
    )
    (net (code "155") (name "unconnected-(J1-USER0-Pad47)") (class "Default")
      (node (ref "J1") (pin "47") (pinfunction "USER0_47") (pintype "bidirectional"))
    )
    (net (code "156") (name "unconnected-(J1-USER1-Pad48)") (class "Default")
      (node (ref "J1") (pin "48") (pinfunction "USER1_48") (pintype "bidirectional"))
    )
    (net (code "157") (name "unconnected-(J1-USER2-Pad49)") (class "Default")
      (node (ref "J1") (pin "49") (pinfunction "USER2_49") (pintype "bidirectional"))
    )
    (net (code "158") (name "unconnected-(J1-USER3-Pad50)") (class "Default")
      (node (ref "J1") (pin "50") (pinfunction "USER3_50") (pintype "bidirectional"))
    )
    (net (code "159") (name "unconnected-(J1-USER4-Pad51)") (class "Default")
      (node (ref "J1") (pin "51") (pinfunction "USER4_51") (pintype "bidirectional"))
    )
    (net (code "160") (name "unconnected-(J1-USER5-Pad52)") (class "Default")
      (node (ref "J1") (pin "52") (pinfunction "USER5_52") (pintype "bidirectional"))
    )
    (net (code "161") (name "unconnected-(J1-USER6-Pad99)") (class "Default")
      (node (ref "J1") (pin "99") (pinfunction "USER6_99") (pintype "bidirectional"))
    )
    (net (code "162") (name "unconnected-(J1-USER7-Pad100)") (class "Default")
      (node (ref "J1") (pin "100") (pinfunction "USER7_100") (pintype "bidirectional"))
    )
    (net (code "163") (name "unconnected-(J1-USER8-Pad101)") (class "Default")
      (node (ref "J1") (pin "101") (pinfunction "USER8_101") (pintype "bidirectional"))
    )
    (net (code "164") (name "unconnected-(J1-USER9-Pad102)") (class "Default")
      (node (ref "J1") (pin "102") (pinfunction "USER9_102") (pintype "bidirectional"))
    )
    (net (code "165") (name "unconnected-(J1-USER10-Pad103)") (class "Default")
      (node (ref "J1") (pin "103") (pinfunction "USER10_103") (pintype "bidirectional"))
    )
    (net (code "166") (name "unconnected-(J1-USER11-Pad104)") (class "Default")
      (node (ref "J1") (pin "104") (pinfunction "USER11_104") (pintype "bidirectional"))
    )
    (net (code "167") (name "unconnected-(J1-VBACKUP-Pad42)") (class "Default")
      (node (ref "J1") (pin "42") (pinfunction "VBACKUP_42") (pintype "bidirectional"))
    )
    (net (code "168") (name "unconnected-(J1-VBATT-Pad97)") (class "Default")
      (node (ref "J1") (pin "97") (pinfunction "VBATT_97") (pintype "bidirectional"))
    )
    (net (code "169") (name "unconnected-(J1-VBATT-Pad98)") (class "Default")
      (node (ref "J1") (pin "98") (pinfunction "VBATT_98") (pintype "bidirectional"))
    )
    (net (code "170") (name "unconnected-(J1-VCC_SYS-Pad79)") (class "Default")
      (node (ref "J1") (pin "79") (pinfunction "VCC_SYS_79") (pintype "bidirectional"))
    )
    (net (code "171") (name "unconnected-(J1-VCC_SYS-Pad80)") (class "Default")
      (node (ref "J1") (pin "80") (pinfunction "VCC_SYS_80") (pintype "bidirectional"))
    )
    (net (code "172") (name "unconnected-(J1-VEREF+-Pad28)") (class "Default")
      (node (ref "J1") (pin "28") (pinfunction "VEREF+_28") (pintype "bidirectional"))
    )
    (net (code "173") (name "unconnected-(J1-VREF+-Pad26)") (class "Default")
      (node (ref "J1") (pin "26") (pinfunction "VREF+_26") (pintype "bidirectional"))
    )
    (net (code "174") (name "unconnected-(J1-VREF--Pad30)") (class "Default")
      (node (ref "J1") (pin "30") (pinfunction "VREF-_30") (pintype "bidirectional"))
    )
    (net (code "175") (name "unconnected-(J2-Pad3)") (class "Default")
      (node (ref "J2") (pin "3") (pinfunction "3_3") (pintype "bidirectional"))
    )
    (net (code "176") (name "unconnected-(J2-Pad6)") (class "Default")
      (node (ref "J2") (pin "6") (pinfunction "6_6") (pintype "bidirectional"))
    )
    (net (code "177") (name "unconnected-(J4-Pad2)") (class "Default")
      (node (ref "J4") (pin "2") (pinfunction "2_2") (pintype "bidirectional"))
    )
    (net (code "178") (name "unconnected-(J4-Pad5)") (class "Default")
      (node (ref "J4") (pin "5") (pinfunction "5_5") (pintype "bidirectional"))
    )
    (net (code "179") (name "unconnected-(J5-Pad2)") (class "Default")
      (node (ref "J5") (pin "2") (pinfunction "2_2") (pintype "bidirectional"))
    )
    (net (code "180") (name "unconnected-(J5-Pad5)") (class "Default")
      (node (ref "J5") (pin "5") (pinfunction "5_5") (pintype "bidirectional"))
    )
    (net (code "181") (name "unconnected-(OK1-A2-Pad3)") (class "Default")
      (node (ref "OK1") (pin "3") (pinfunction "A2_3") (pintype "bidirectional"))
    )
    (net (code "182") (name "unconnected-(OK1-A3-Pad5)") (class "Default")
      (node (ref "OK1") (pin "5") (pinfunction "A3_5") (pintype "bidirectional"))
    )
    (net (code "183") (name "unconnected-(OK1-A4-Pad7)") (class "Default")
      (node (ref "OK1") (pin "7") (pinfunction "A4_7") (pintype "bidirectional"))
    )
    (net (code "184") (name "unconnected-(OK1-C2-Pad14)") (class "Default")
      (node (ref "OK1") (pin "14") (pinfunction "C2_14") (pintype "bidirectional"))
    )
    (net (code "185") (name "unconnected-(OK1-C3-Pad12)") (class "Default")
      (node (ref "OK1") (pin "12") (pinfunction "C3_12") (pintype "bidirectional"))
    )
    (net (code "186") (name "unconnected-(OK1-C4-Pad10)") (class "Default")
      (node (ref "OK1") (pin "10") (pinfunction "C4_10") (pintype "bidirectional"))
    )
    (net (code "187") (name "unconnected-(OK1-E2-Pad13)") (class "Default")
      (node (ref "OK1") (pin "13") (pinfunction "E2_13") (pintype "bidirectional"))
    )
    (net (code "188") (name "unconnected-(OK1-E3-Pad11)") (class "Default")
      (node (ref "OK1") (pin "11") (pinfunction "E3_11") (pintype "bidirectional"))
    )
    (net (code "189") (name "unconnected-(OK1-E4-Pad9)") (class "Default")
      (node (ref "OK1") (pin "9") (pinfunction "E4_9") (pintype "bidirectional"))
    )
    (net (code "190") (name "unconnected-(OK1-K2-Pad4)") (class "Default")
      (node (ref "OK1") (pin "4") (pinfunction "K2_4") (pintype "bidirectional"))
    )
    (net (code "191") (name "unconnected-(OK1-K3-Pad6)") (class "Default")
      (node (ref "OK1") (pin "6") (pinfunction "K3_6") (pintype "bidirectional"))
    )
    (net (code "192") (name "unconnected-(OK1-K4-Pad8)") (class "Default")
      (node (ref "OK1") (pin "8") (pinfunction "K4_8") (pintype "bidirectional"))
    )
    (net (code "193") (name "unconnected-(U1-COMP-PadB7)") (class "Default")
      (node (ref "U1") (pin "B7") (pinfunction "COMP_B7") (pintype "bidirectional"))
    )
    (net (code "194") (name "unconnected-(U1-EXTV_CC-PadF6)") (class "Default")
      (node (ref "U1") (pin "F6") (pinfunction "EXTV_CC_F6") (pintype "bidirectional"))
    )
    (net (code "195") (name "unconnected-(U1-PGOOD-PadB5)") (class "Default")
      (node (ref "U1") (pin "B5") (pinfunction "PGOOD_B5") (pintype "bidirectional"))
    )
    (net (code "196") (name "unconnected-(U1-PLLIN-PadB9)") (class "Default")
      (node (ref "U1") (pin "B9") (pinfunction "PLLIN_B9") (pintype "bidirectional"))
    )
    (net (code "197") (name "unconnected-(U1-SS-PadA6)") (class "Default")
      (node (ref "U1") (pin "A6") (pinfunction "SS_A6") (pintype "bidirectional"))
    )
    (net (code "198") (name "unconnected-(U1-STBYMD-PadA10)") (class "Default")
      (node (ref "U1") (pin "A10") (pinfunction "STBYMD_A10") (pintype "bidirectional"))
    )
    (net (code "199") (name "unconnected-(U2-ADC_IN0-Pad2)") (class "Default")
      (node (ref "U2") (pin "2") (pinfunction "ADC_IN0_2") (pintype "bidirectional"))
    )
    (net (code "200") (name "unconnected-(U2-ADC_IN1-Pad1)") (class "Default")
      (node (ref "U2") (pin "1") (pinfunction "ADC_IN1_1") (pintype "bidirectional"))
    )
    (net (code "201") (name "unconnected-(U2-ADC_IN2-Pad4)") (class "Default")
      (node (ref "U2") (pin "4") (pinfunction "ADC_IN2_4") (pintype "bidirectional"))
    )
    (net (code "202") (name "unconnected-(U2-ADC_IN3-Pad3)") (class "Default")
      (node (ref "U2") (pin "3") (pinfunction "ADC_IN3_3") (pintype "bidirectional"))
    )
    (net (code "203") (name "unconnected-(U2-ADC_IN4-Pad6)") (class "Default")
      (node (ref "U2") (pin "6") (pinfunction "ADC_IN4_6") (pintype "bidirectional"))
    )
    (net (code "204") (name "unconnected-(U2-ADC_IN7-Pad5)") (class "Default")
      (node (ref "U2") (pin "5") (pinfunction "ADC_IN7_5") (pintype "bidirectional"))
    )
    (net (code "205") (name "unconnected-(U2-AGND-Pad8)") (class "Default")
      (node (ref "U2") (pin "8") (pinfunction "AGND_8") (pintype "bidirectional"))
    )
    (net (code "206") (name "unconnected-(U2-CAN1_RX-Pad20)") (class "Default")
      (node (ref "U2") (pin "20") (pinfunction "CAN1_RX_20") (pintype "bidirectional"))
    )
    (net (code "207") (name "unconnected-(U2-CAN1_TX-Pad22)") (class "Default")
      (node (ref "U2") (pin "22") (pinfunction "CAN1_TX_22") (pintype "bidirectional"))
    )
    (net (code "208") (name "unconnected-(U2-ERX_JM-Pad44)") (class "Default")
      (node (ref "U2") (pin "44") (pinfunction "ERX_JM_44") (pintype "bidirectional"))
    )
    (net (code "209") (name "unconnected-(U2-ERX_JP-Pad43)") (class "Default")
      (node (ref "U2") (pin "43") (pinfunction "ERX_JP_43") (pintype "bidirectional"))
    )
    (net (code "210") (name "unconnected-(U2-ETX_JM-Pad46)") (class "Default")
      (node (ref "U2") (pin "46") (pinfunction "ETX_JM_46") (pintype "bidirectional"))
    )
    (net (code "211") (name "unconnected-(U2-ETX_JP-Pad45)") (class "Default")
      (node (ref "U2") (pin "45") (pinfunction "ETX_JP_45") (pintype "bidirectional"))
    )
    (net (code "212") (name "unconnected-(U2-IRQ2-Pad50)") (class "Default")
      (node (ref "U2") (pin "50") (pinfunction "IRQ2_50") (pintype "bidirectional"))
    )
    (net (code "213") (name "unconnected-(U2-IRQ3-Pad49)") (class "Default")
      (node (ref "U2") (pin "49") (pinfunction "IRQ3_49") (pintype "bidirectional"))
    )
    (net (code "214") (name "unconnected-(U2-IRQ7-Pad9)") (class "Default")
      (node (ref "U2") (pin "9") (pinfunction "IRQ7_9") (pintype "bidirectional"))
    )
    (net (code "215") (name "unconnected-(U2-LINKLED-Pad42)") (class "Default")
      (node (ref "U2") (pin "42") (pinfunction "LINKLED_42") (pintype "bidirectional"))
    )
    (net (code "216") (name "unconnected-(U2-OW_DAT-Pad12)") (class "Default")
      (node (ref "U2") (pin "12") (pinfunction "OW_DAT_12") (pintype "bidirectional"))
    )
    (net (code "217") (name "unconnected-(U2-RSTI-Pad11)") (class "Default")
      (node (ref "U2") (pin "11") (pinfunction "RSTI_11") (pintype "bidirectional"))
    )
    (net (code "218") (name "unconnected-(U2-SDHC_DAT3-Pad15)") (class "Default")
      (node (ref "U2") (pin "15") (pinfunction "SDHC_DAT3_15") (pintype "bidirectional"))
    )
    (net (code "219") (name "unconnected-(U2-SPEEDLED-Pad40)") (class "Default")
      (node (ref "U2") (pin "40") (pinfunction "SPEEDLED_40") (pintype "bidirectional"))
    )
    (net (code "220") (name "unconnected-(U2-T0IN-Pad19)") (class "Default")
      (node (ref "U2") (pin "19") (pinfunction "T0IN_19") (pintype "bidirectional"))
    )
    (net (code "221") (name "unconnected-(U2-T1IN-Pad21)") (class "Default")
      (node (ref "U2") (pin "21") (pinfunction "T1IN_21") (pintype "bidirectional"))
    )
    (net (code "222") (name "unconnected-(U2-T3IN-Pad25)") (class "Default")
      (node (ref "U2") (pin "25") (pinfunction "T3IN_25") (pintype "bidirectional"))
    )
    (net (code "223") (name "unconnected-(U2-UART0_CTS-Pad30)") (class "Default")
      (node (ref "U2") (pin "30") (pinfunction "UART0_CTS_30") (pintype "bidirectional"))
    )
    (net (code "224") (name "unconnected-(U2-UART0_RTS-Pad28)") (class "Default")
      (node (ref "U2") (pin "28") (pinfunction "UART0_RTS_28") (pintype "bidirectional"))
    )
    (net (code "225") (name "unconnected-(U2-UART0_RX-Pad24)") (class "Default")
      (node (ref "U2") (pin "24") (pinfunction "UART0_RX_24") (pintype "bidirectional"))
    )
    (net (code "226") (name "unconnected-(U2-UART0_TX-Pad26)") (class "Default")
      (node (ref "U2") (pin "26") (pinfunction "UART0_TX_26") (pintype "bidirectional"))
    )
    (net (code "227") (name "unconnected-(U2-UART2_CTS-Pad10)") (class "Default")
      (node (ref "U2") (pin "10") (pinfunction "UART2_CTS_10") (pintype "bidirectional"))
    )
    (net (code "228") (name "unconnected-(U2-UART2_RTS-Pad14)") (class "Default")
      (node (ref "U2") (pin "14") (pinfunction "UART2_RTS_14") (pintype "bidirectional"))
    )
    (net (code "229") (name "unconnected-(U2-UART2_RX-Pad13)") (class "Default")
      (node (ref "U2") (pin "13") (pinfunction "UART2_RX_13") (pintype "bidirectional"))
    )
    (net (code "230") (name "unconnected-(U2-UART2_TX-Pad16)") (class "Default")
      (node (ref "U2") (pin "16") (pinfunction "UART2_TX_16") (pintype "bidirectional"))
    )
    (net (code "231") (name "unconnected-(U2-USBO_DM-Pad51)") (class "Default")
      (node (ref "U2") (pin "51") (pinfunction "USBO_DM_51") (pintype "bidirectional"))
    )
    (net (code "232") (name "unconnected-(U2-USBO_DP-Pad52)") (class "Default")
      (node (ref "U2") (pin "52") (pinfunction "USBO_DP_52") (pintype "bidirectional"))
    )
    (net (code "233") (name "unconnected-(U2-VCC3VE-Pad41)") (class "Default")
      (node (ref "U2") (pin "41") (pinfunction "VCC3VE_41") (pintype "bidirectional"))
    )
    (net (code "234") (name "unconnected-(U2-VDDA_DAC_ADC-Pad7)") (class "Default")
      (node (ref "U2") (pin "7") (pinfunction "VDDA_DAC_ADC_7") (pintype "bidirectional"))
    )
    (net (code "235") (name "unconnected-(U3-TIMER1-Pad2)") (class "Default")
      (node (ref "U3") (pin "2") (pinfunction "TIMER1_2") (pintype "bidirectional"))
    )
    (net (code "236") (name "unconnected-(U3-TIMER2-Pad4)") (class "Default")
      (node (ref "U3") (pin "4") (pinfunction "TIMER2_4") (pintype "bidirectional"))
    )
    (net (code "237") (name "unconnected-(U3-TIMER3-Pad6)") (class "Default")
      (node (ref "U3") (pin "6") (pinfunction "TIMER3_6") (pintype "bidirectional"))
    )
    (net (code "238") (name "unconnected-(U3-TIMER4-Pad8)") (class "Default")
      (node (ref "U3") (pin "8") (pinfunction "TIMER4_8") (pintype "bidirectional"))
    )
    (net (code "239") (name "unconnected-(U4-TIMER1-Pad2)") (class "Default")
      (node (ref "U4") (pin "2") (pinfunction "TIMER1_2") (pintype "bidirectional"))
    )
    (net (code "240") (name "unconnected-(U4-TIMER2-Pad4)") (class "Default")
      (node (ref "U4") (pin "4") (pinfunction "TIMER2_4") (pintype "bidirectional"))
    )
    (net (code "241") (name "unconnected-(U4-TIMER3-Pad6)") (class "Default")
      (node (ref "U4") (pin "6") (pinfunction "TIMER3_6") (pintype "bidirectional"))
    )
    (net (code "242") (name "unconnected-(U4-TIMER4-Pad8)") (class "Default")
      (node (ref "U4") (pin "8") (pinfunction "TIMER4_8") (pintype "bidirectional"))
    )
  )
)
